# Cube_Mini_8x8x8_LED_Grid_08.net
KiCad netlist of a schematic drawn in EAGLE
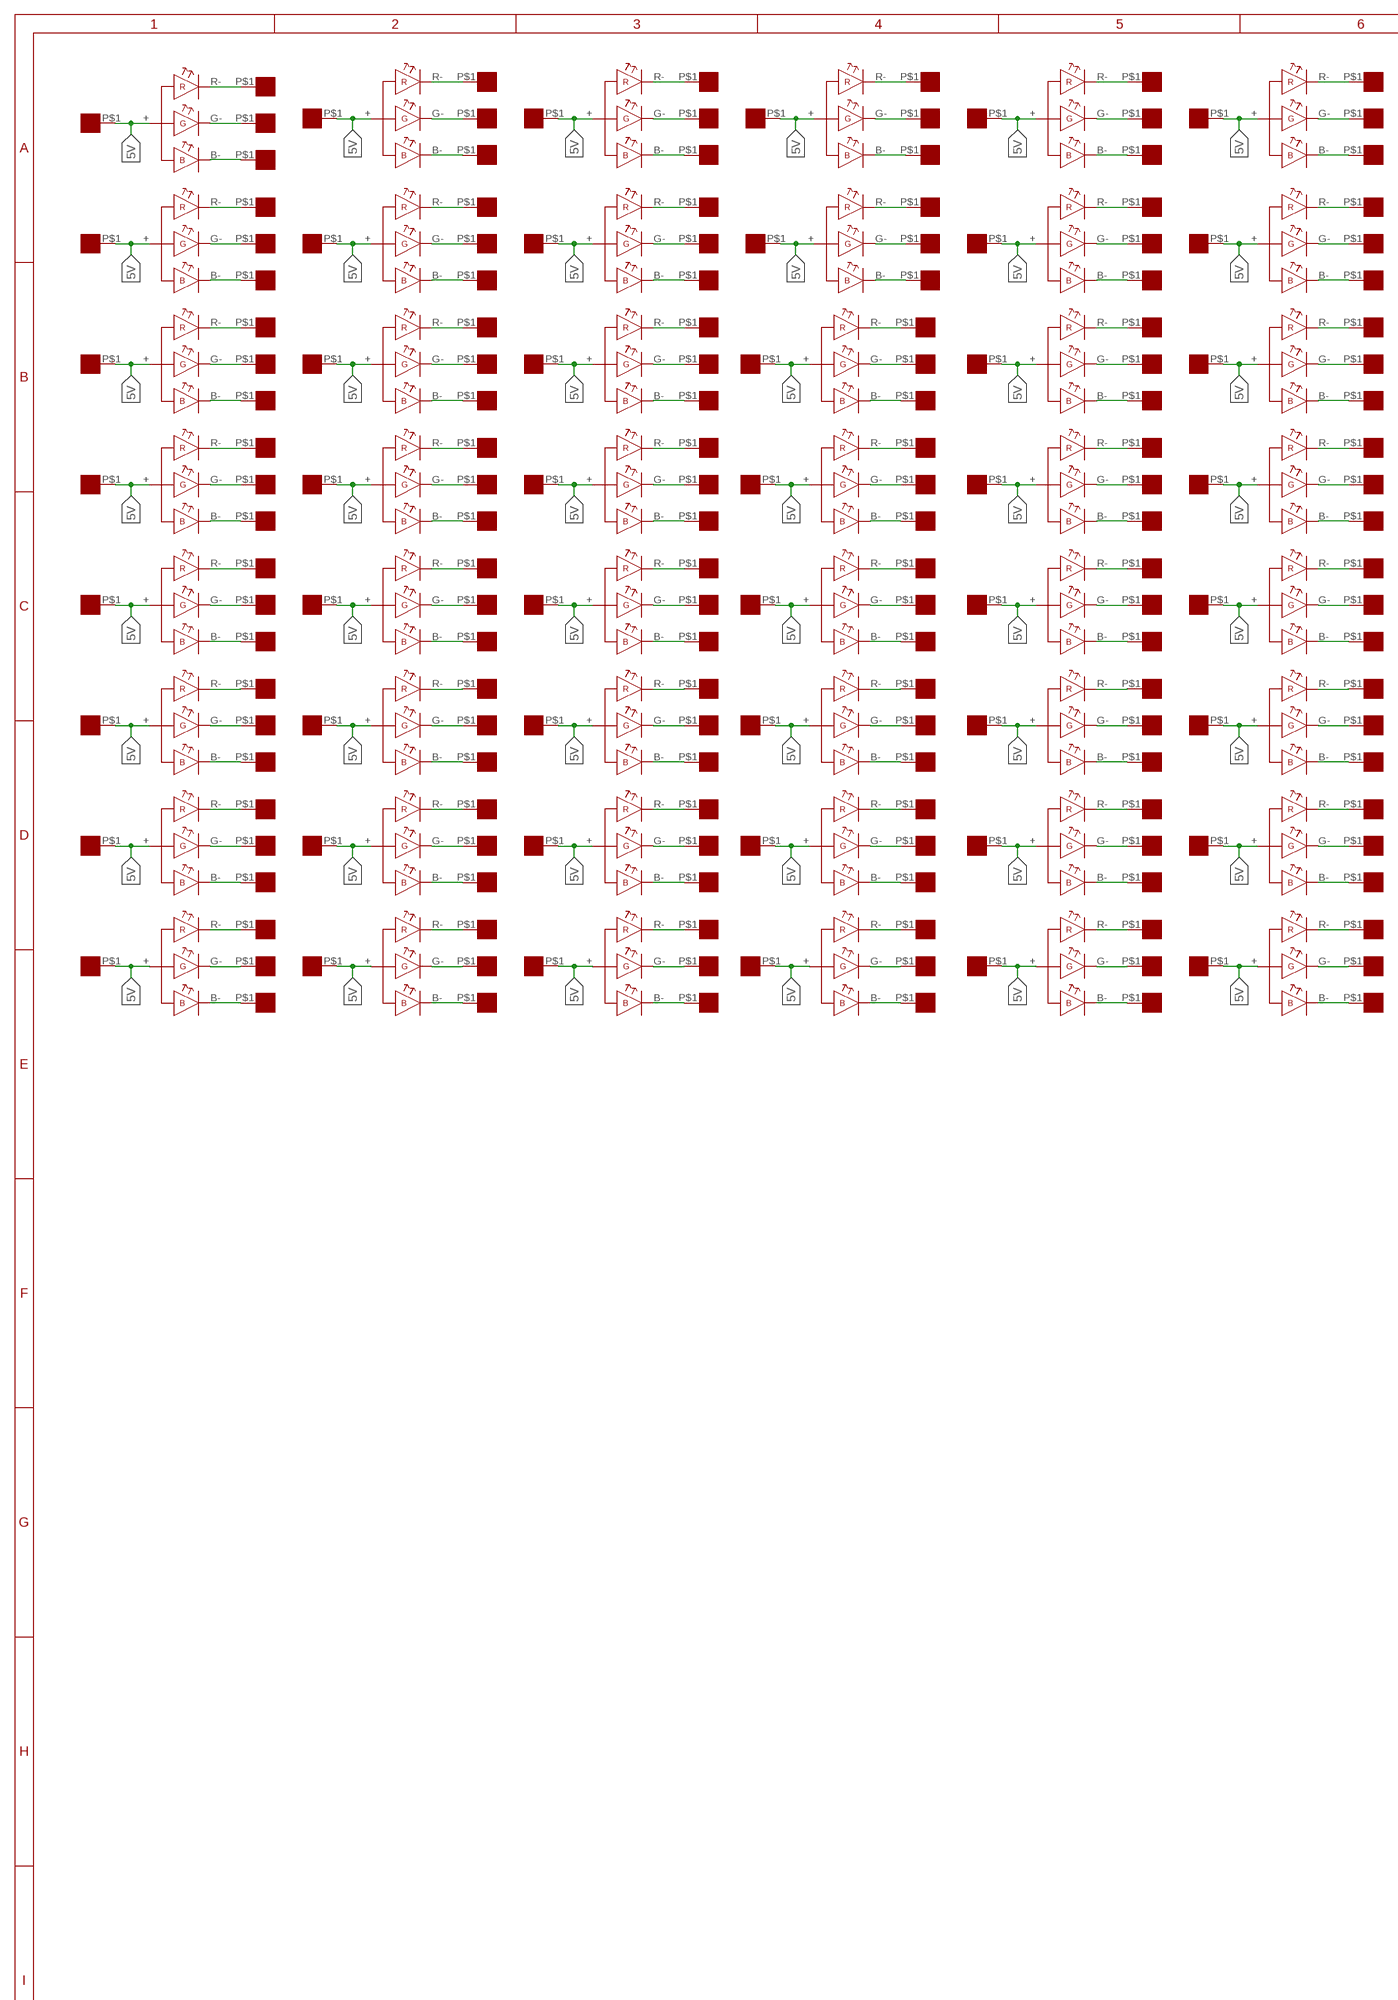
[diagram p0: schematic, sheet 1, part 1 of 2]
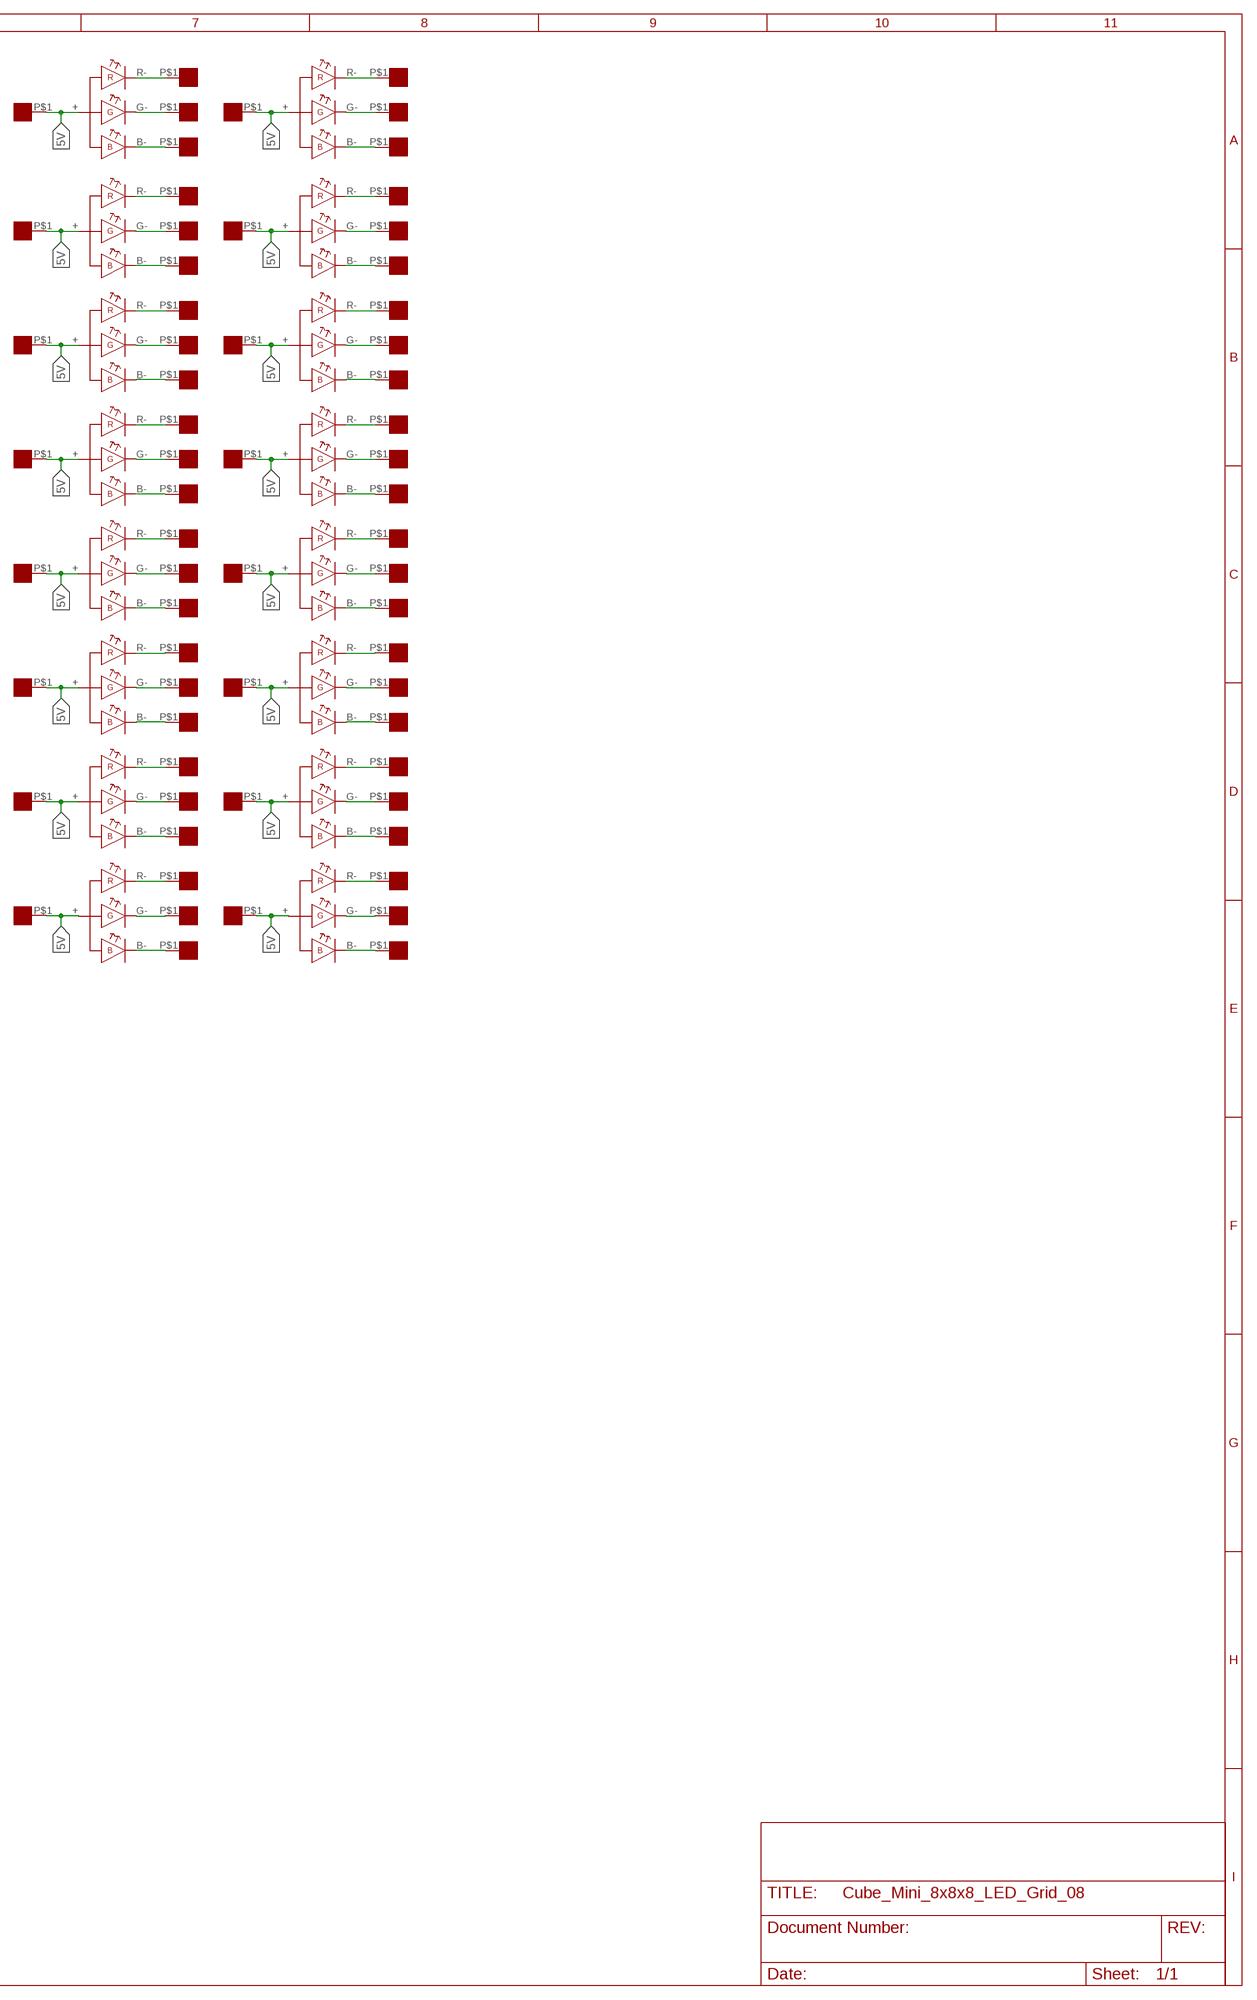
[diagram p1: schematic, sheet 1, part 2 of 2]

(export (version "E")
  (design (tool "Eeschema 10.0.6"))
  (components
    (comp (ref "5V$1")
      (value "05X08PAD")
      (footprint "eagle-import:05X08PAD")
      (libsource (lib "eagle-import") (part "05X08PAD"))
    )
    (comp (ref "5V$2")
      (value "05X08PAD")
      (footprint "eagle-import:05X08PAD")
      (libsource (lib "eagle-import") (part "05X08PAD"))
    )
    (comp (ref "5V$3")
      (value "05X08PAD")
      (footprint "eagle-import:05X08PAD")
      (libsource (lib "eagle-import") (part "05X08PAD"))
    )
    (comp (ref "5V$4")
      (value "05X08PAD")
      (footprint "eagle-import:05X08PAD")
      (libsource (lib "eagle-import") (part "05X08PAD"))
    )
    (comp (ref "5V$5")
      (value "05X08PAD")
      (footprint "eagle-import:05X08PAD")
      (libsource (lib "eagle-import") (part "05X08PAD"))
    )
    (comp (ref "5V$6")
      (value "05X08PAD")
      (footprint "eagle-import:05X08PAD")
      (libsource (lib "eagle-import") (part "05X08PAD"))
    )
    (comp (ref "5V$7")
      (value "05X08PAD")
      (footprint "eagle-import:05X08PAD")
      (libsource (lib "eagle-import") (part "05X08PAD"))
    )
    (comp (ref "5V$8")
      (value "05X08PAD")
      (footprint "eagle-import:05X08PAD")
      (libsource (lib "eagle-import") (part "05X08PAD"))
    )
    (comp (ref "5V$9")
      (value "05X08PAD")
      (footprint "eagle-import:05X08PAD")
      (libsource (lib "eagle-import") (part "05X08PAD"))
    )
    (comp (ref "5V$10")
      (value "05X08PAD")
      (footprint "eagle-import:05X08PAD")
      (libsource (lib "eagle-import") (part "05X08PAD"))
    )
    (comp (ref "5V$11")
      (value "05X08PAD")
      (footprint "eagle-import:05X08PAD")
      (libsource (lib "eagle-import") (part "05X08PAD"))
    )
    (comp (ref "5V$12")
      (value "05X08PAD")
      (footprint "eagle-import:05X08PAD")
      (libsource (lib "eagle-import") (part "05X08PAD"))
    )
    (comp (ref "5V$13")
      (value "05X08PAD")
      (footprint "eagle-import:05X08PAD")
      (libsource (lib "eagle-import") (part "05X08PAD"))
    )
    (comp (ref "5V$14")
      (value "05X08PAD")
      (footprint "eagle-import:05X08PAD")
      (libsource (lib "eagle-import") (part "05X08PAD"))
    )
    (comp (ref "5V$15")
      (value "05X08PAD")
      (footprint "eagle-import:05X08PAD")
      (libsource (lib "eagle-import") (part "05X08PAD"))
    )
    (comp (ref "5V$16")
      (value "05X08PAD")
      (footprint "eagle-import:05X08PAD")
      (libsource (lib "eagle-import") (part "05X08PAD"))
    )
    (comp (ref "5V$17")
      (value "05X08PAD")
      (footprint "eagle-import:05X08PAD")
      (libsource (lib "eagle-import") (part "05X08PAD"))
    )
    (comp (ref "5V$18")
      (value "05X08PAD")
      (footprint "eagle-import:05X08PAD")
      (libsource (lib "eagle-import") (part "05X08PAD"))
    )
    (comp (ref "5V$19")
      (value "05X08PAD")
      (footprint "eagle-import:05X08PAD")
      (libsource (lib "eagle-import") (part "05X08PAD"))
    )
    (comp (ref "5V$20")
      (value "05X08PAD")
      (footprint "eagle-import:05X08PAD")
      (libsource (lib "eagle-import") (part "05X08PAD"))
    )
    (comp (ref "5V$21")
      (value "05X08PAD")
      (footprint "eagle-import:05X08PAD")
      (libsource (lib "eagle-import") (part "05X08PAD"))
    )
    (comp (ref "5V$22")
      (value "05X08PAD")
      (footprint "eagle-import:05X08PAD")
      (libsource (lib "eagle-import") (part "05X08PAD"))
    )
    (comp (ref "5V$23")
      (value "05X08PAD")
      (footprint "eagle-import:05X08PAD")
      (libsource (lib "eagle-import") (part "05X08PAD"))
    )
    (comp (ref "5V$24")
      (value "05X08PAD")
      (footprint "eagle-import:05X08PAD")
      (libsource (lib "eagle-import") (part "05X08PAD"))
    )
    (comp (ref "5V$25")
      (value "05X08PAD")
      (footprint "eagle-import:05X08PAD")
      (libsource (lib "eagle-import") (part "05X08PAD"))
    )
    (comp (ref "5V$26")
      (value "05X08PAD")
      (footprint "eagle-import:05X08PAD")
      (libsource (lib "eagle-import") (part "05X08PAD"))
    )
    (comp (ref "5V$27")
      (value "05X08PAD")
      (footprint "eagle-import:05X08PAD")
      (libsource (lib "eagle-import") (part "05X08PAD"))
    )
    (comp (ref "5V$28")
      (value "05X08PAD")
      (footprint "eagle-import:05X08PAD")
      (libsource (lib "eagle-import") (part "05X08PAD"))
    )
    (comp (ref "5V$29")
      (value "05X08PAD")
      (footprint "eagle-import:05X08PAD")
      (libsource (lib "eagle-import") (part "05X08PAD"))
    )
    (comp (ref "5V$30")
      (value "05X08PAD")
      (footprint "eagle-import:05X08PAD")
      (libsource (lib "eagle-import") (part "05X08PAD"))
    )
    (comp (ref "5V$31")
      (value "05X08PAD")
      (footprint "eagle-import:05X08PAD")
      (libsource (lib "eagle-import") (part "05X08PAD"))
    )
    (comp (ref "5V$32")
      (value "05X08PAD")
      (footprint "eagle-import:05X08PAD")
      (libsource (lib "eagle-import") (part "05X08PAD"))
    )
    (comp (ref "5V$33")
      (value "05X08PAD")
      (footprint "eagle-import:05X08PAD")
      (libsource (lib "eagle-import") (part "05X08PAD"))
    )
    (comp (ref "5V$34")
      (value "05X08PAD")
      (footprint "eagle-import:05X08PAD")
      (libsource (lib "eagle-import") (part "05X08PAD"))
    )
    (comp (ref "5V$35")
      (value "05X08PAD")
      (footprint "eagle-import:05X08PAD")
      (libsource (lib "eagle-import") (part "05X08PAD"))
    )
    (comp (ref "5V$36")
      (value "05X08PAD")
      (footprint "eagle-import:05X08PAD")
      (libsource (lib "eagle-import") (part "05X08PAD"))
    )
    (comp (ref "5V$37")
      (value "05X08PAD")
      (footprint "eagle-import:05X08PAD")
      (libsource (lib "eagle-import") (part "05X08PAD"))
    )
    (comp (ref "5V$38")
      (value "05X08PAD")
      (footprint "eagle-import:05X08PAD")
      (libsource (lib "eagle-import") (part "05X08PAD"))
    )
    (comp (ref "5V$39")
      (value "05X08PAD")
      (footprint "eagle-import:05X08PAD")
      (libsource (lib "eagle-import") (part "05X08PAD"))
    )
    (comp (ref "5V$40")
      (value "05X08PAD")
      (footprint "eagle-import:05X08PAD")
      (libsource (lib "eagle-import") (part "05X08PAD"))
    )
    (comp (ref "5V$41")
      (value "05X08PAD")
      (footprint "eagle-import:05X08PAD")
      (libsource (lib "eagle-import") (part "05X08PAD"))
    )
    (comp (ref "5V$42")
      (value "05X08PAD")
      (footprint "eagle-import:05X08PAD")
      (libsource (lib "eagle-import") (part "05X08PAD"))
    )
    (comp (ref "5V$43")
      (value "05X08PAD")
      (footprint "eagle-import:05X08PAD")
      (libsource (lib "eagle-import") (part "05X08PAD"))
    )
    (comp (ref "5V$44")
      (value "05X08PAD")
      (footprint "eagle-import:05X08PAD")
      (libsource (lib "eagle-import") (part "05X08PAD"))
    )
    (comp (ref "5V$45")
      (value "05X08PAD")
      (footprint "eagle-import:05X08PAD")
      (libsource (lib "eagle-import") (part "05X08PAD"))
    )
    (comp (ref "5V$46")
      (value "05X08PAD")
      (footprint "eagle-import:05X08PAD")
      (libsource (lib "eagle-import") (part "05X08PAD"))
    )
    (comp (ref "5V$47")
      (value "05X08PAD")
      (footprint "eagle-import:05X08PAD")
      (libsource (lib "eagle-import") (part "05X08PAD"))
    )
    (comp (ref "5V$48")
      (value "05X08PAD")
      (footprint "eagle-import:05X08PAD")
      (libsource (lib "eagle-import") (part "05X08PAD"))
    )
    (comp (ref "5V$49")
      (value "05X08PAD")
      (footprint "eagle-import:05X08PAD")
      (libsource (lib "eagle-import") (part "05X08PAD"))
    )
    (comp (ref "5V$50")
      (value "05X08PAD")
      (footprint "eagle-import:05X08PAD")
      (libsource (lib "eagle-import") (part "05X08PAD"))
    )
    (comp (ref "5V$51")
      (value "05X08PAD")
      (footprint "eagle-import:05X08PAD")
      (libsource (lib "eagle-import") (part "05X08PAD"))
    )
    (comp (ref "5V$52")
      (value "05X08PAD")
      (footprint "eagle-import:05X08PAD")
      (libsource (lib "eagle-import") (part "05X08PAD"))
    )
    (comp (ref "5V$53")
      (value "05X08PAD")
      (footprint "eagle-import:05X08PAD")
      (libsource (lib "eagle-import") (part "05X08PAD"))
    )
    (comp (ref "5V$54")
      (value "05X08PAD")
      (footprint "eagle-import:05X08PAD")
      (libsource (lib "eagle-import") (part "05X08PAD"))
    )
    (comp (ref "5V$55")
      (value "05X08PAD")
      (footprint "eagle-import:05X08PAD")
      (libsource (lib "eagle-import") (part "05X08PAD"))
    )
    (comp (ref "5V$56")
      (value "05X08PAD")
      (footprint "eagle-import:05X08PAD")
      (libsource (lib "eagle-import") (part "05X08PAD"))
    )
    (comp (ref "5V$57")
      (value "05X08PAD")
      (footprint "eagle-import:05X08PAD")
      (libsource (lib "eagle-import") (part "05X08PAD"))
    )
    (comp (ref "5V$58")
      (value "05X08PAD")
      (footprint "eagle-import:05X08PAD")
      (libsource (lib "eagle-import") (part "05X08PAD"))
    )
    (comp (ref "5V$59")
      (value "05X08PAD")
      (footprint "eagle-import:05X08PAD")
      (libsource (lib "eagle-import") (part "05X08PAD"))
    )
    (comp (ref "5V$60")
      (value "05X08PAD")
      (footprint "eagle-import:05X08PAD")
      (libsource (lib "eagle-import") (part "05X08PAD"))
    )
    (comp (ref "5V$61")
      (value "05X08PAD")
      (footprint "eagle-import:05X08PAD")
      (libsource (lib "eagle-import") (part "05X08PAD"))
    )
    (comp (ref "5V$62")
      (value "05X08PAD")
      (footprint "eagle-import:05X08PAD")
      (libsource (lib "eagle-import") (part "05X08PAD"))
    )
    (comp (ref "5V$63")
      (value "05X08PAD")
      (footprint "eagle-import:05X08PAD")
      (libsource (lib "eagle-import") (part "05X08PAD"))
    )
    (comp (ref "5V$64")
      (value "05X08PAD")
      (footprint "eagle-import:05X08PAD")
      (libsource (lib "eagle-import") (part "05X08PAD"))
    )
    (comp (ref "B$1")
      (value "05X08PAD")
      (footprint "eagle-import:05X08PAD")
      (libsource (lib "eagle-import") (part "05X08PAD"))
    )
    (comp (ref "B$2")
      (value "05X08PAD")
      (footprint "eagle-import:05X08PAD")
      (libsource (lib "eagle-import") (part "05X08PAD"))
    )
    (comp (ref "B$3")
      (value "05X08PAD")
      (footprint "eagle-import:05X08PAD")
      (libsource (lib "eagle-import") (part "05X08PAD"))
    )
    (comp (ref "B$4")
      (value "05X08PAD")
      (footprint "eagle-import:05X08PAD")
      (libsource (lib "eagle-import") (part "05X08PAD"))
    )
    (comp (ref "B$5")
      (value "05X08PAD")
      (footprint "eagle-import:05X08PAD")
      (libsource (lib "eagle-import") (part "05X08PAD"))
    )
    (comp (ref "B$6")
      (value "05X08PAD")
      (footprint "eagle-import:05X08PAD")
      (libsource (lib "eagle-import") (part "05X08PAD"))
    )
    (comp (ref "B$7")
      (value "05X08PAD")
      (footprint "eagle-import:05X08PAD")
      (libsource (lib "eagle-import") (part "05X08PAD"))
    )
    (comp (ref "B$8")
      (value "05X08PAD")
      (footprint "eagle-import:05X08PAD")
      (libsource (lib "eagle-import") (part "05X08PAD"))
    )
    (comp (ref "B$9")
      (value "05X08PAD")
      (footprint "eagle-import:05X08PAD")
      (libsource (lib "eagle-import") (part "05X08PAD"))
    )
    (comp (ref "B$10")
      (value "05X08PAD")
      (footprint "eagle-import:05X08PAD")
      (libsource (lib "eagle-import") (part "05X08PAD"))
    )
    (comp (ref "B$11")
      (value "05X08PAD")
      (footprint "eagle-import:05X08PAD")
      (libsource (lib "eagle-import") (part "05X08PAD"))
    )
    (comp (ref "B$12")
      (value "05X08PAD")
      (footprint "eagle-import:05X08PAD")
      (libsource (lib "eagle-import") (part "05X08PAD"))
    )
    (comp (ref "B$13")
      (value "05X08PAD")
      (footprint "eagle-import:05X08PAD")
      (libsource (lib "eagle-import") (part "05X08PAD"))
    )
    (comp (ref "B$14")
      (value "05X08PAD")
      (footprint "eagle-import:05X08PAD")
      (libsource (lib "eagle-import") (part "05X08PAD"))
    )
    (comp (ref "B$15")
      (value "05X08PAD")
      (footprint "eagle-import:05X08PAD")
      (libsource (lib "eagle-import") (part "05X08PAD"))
    )
    (comp (ref "B$16")
      (value "05X08PAD")
      (footprint "eagle-import:05X08PAD")
      (libsource (lib "eagle-import") (part "05X08PAD"))
    )
    (comp (ref "B$17")
      (value "05X08PAD")
      (footprint "eagle-import:05X08PAD")
      (libsource (lib "eagle-import") (part "05X08PAD"))
    )
    (comp (ref "B$18")
      (value "05X08PAD")
      (footprint "eagle-import:05X08PAD")
      (libsource (lib "eagle-import") (part "05X08PAD"))
    )
    (comp (ref "B$19")
      (value "05X08PAD")
      (footprint "eagle-import:05X08PAD")
      (libsource (lib "eagle-import") (part "05X08PAD"))
    )
    (comp (ref "B$20")
      (value "05X08PAD")
      (footprint "eagle-import:05X08PAD")
      (libsource (lib "eagle-import") (part "05X08PAD"))
    )
    (comp (ref "B$21")
      (value "05X08PAD")
      (footprint "eagle-import:05X08PAD")
      (libsource (lib "eagle-import") (part "05X08PAD"))
    )
    (comp (ref "B$22")
      (value "05X08PAD")
      (footprint "eagle-import:05X08PAD")
      (libsource (lib "eagle-import") (part "05X08PAD"))
    )
    (comp (ref "B$23")
      (value "05X08PAD")
      (footprint "eagle-import:05X08PAD")
      (libsource (lib "eagle-import") (part "05X08PAD"))
    )
    (comp (ref "B$24")
      (value "05X08PAD")
      (footprint "eagle-import:05X08PAD")
      (libsource (lib "eagle-import") (part "05X08PAD"))
    )
    (comp (ref "B$25")
      (value "05X08PAD")
      (footprint "eagle-import:05X08PAD")
      (libsource (lib "eagle-import") (part "05X08PAD"))
    )
    (comp (ref "B$26")
      (value "05X08PAD")
      (footprint "eagle-import:05X08PAD")
      (libsource (lib "eagle-import") (part "05X08PAD"))
    )
    (comp (ref "B$27")
      (value "05X08PAD")
      (footprint "eagle-import:05X08PAD")
      (libsource (lib "eagle-import") (part "05X08PAD"))
    )
    (comp (ref "B$28")
      (value "05X08PAD")
      (footprint "eagle-import:05X08PAD")
      (libsource (lib "eagle-import") (part "05X08PAD"))
    )
    (comp (ref "B$29")
      (value "05X08PAD")
      (footprint "eagle-import:05X08PAD")
      (libsource (lib "eagle-import") (part "05X08PAD"))
    )
    (comp (ref "B$30")
      (value "05X08PAD")
      (footprint "eagle-import:05X08PAD")
      (libsource (lib "eagle-import") (part "05X08PAD"))
    )
    (comp (ref "B$31")
      (value "05X08PAD")
      (footprint "eagle-import:05X08PAD")
      (libsource (lib "eagle-import") (part "05X08PAD"))
    )
    (comp (ref "B$32")
      (value "05X08PAD")
      (footprint "eagle-import:05X08PAD")
      (libsource (lib "eagle-import") (part "05X08PAD"))
    )
    (comp (ref "B$33")
      (value "05X08PAD")
      (footprint "eagle-import:05X08PAD")
      (libsource (lib "eagle-import") (part "05X08PAD"))
    )
    (comp (ref "B$34")
      (value "05X08PAD")
      (footprint "eagle-import:05X08PAD")
      (libsource (lib "eagle-import") (part "05X08PAD"))
    )
    (comp (ref "B$35")
      (value "05X08PAD")
      (footprint "eagle-import:05X08PAD")
      (libsource (lib "eagle-import") (part "05X08PAD"))
    )
    (comp (ref "B$36")
      (value "05X08PAD")
      (footprint "eagle-import:05X08PAD")
      (libsource (lib "eagle-import") (part "05X08PAD"))
    )
    (comp (ref "B$37")
      (value "05X08PAD")
      (footprint "eagle-import:05X08PAD")
      (libsource (lib "eagle-import") (part "05X08PAD"))
    )
    (comp (ref "B$38")
      (value "05X08PAD")
      (footprint "eagle-import:05X08PAD")
      (libsource (lib "eagle-import") (part "05X08PAD"))
    )
    (comp (ref "B$39")
      (value "05X08PAD")
      (footprint "eagle-import:05X08PAD")
      (libsource (lib "eagle-import") (part "05X08PAD"))
    )
    (comp (ref "B$40")
      (value "05X08PAD")
      (footprint "eagle-import:05X08PAD")
      (libsource (lib "eagle-import") (part "05X08PAD"))
    )
    (comp (ref "B$41")
      (value "05X08PAD")
      (footprint "eagle-import:05X08PAD")
      (libsource (lib "eagle-import") (part "05X08PAD"))
    )
    (comp (ref "B$42")
      (value "05X08PAD")
      (footprint "eagle-import:05X08PAD")
      (libsource (lib "eagle-import") (part "05X08PAD"))
    )
    (comp (ref "B$43")
      (value "05X08PAD")
      (footprint "eagle-import:05X08PAD")
      (libsource (lib "eagle-import") (part "05X08PAD"))
    )
    (comp (ref "B$44")
      (value "05X08PAD")
      (footprint "eagle-import:05X08PAD")
      (libsource (lib "eagle-import") (part "05X08PAD"))
    )
    (comp (ref "B$45")
      (value "05X08PAD")
      (footprint "eagle-import:05X08PAD")
      (libsource (lib "eagle-import") (part "05X08PAD"))
    )
    (comp (ref "B$46")
      (value "05X08PAD")
      (footprint "eagle-import:05X08PAD")
      (libsource (lib "eagle-import") (part "05X08PAD"))
    )
    (comp (ref "B$47")
      (value "05X08PAD")
      (footprint "eagle-import:05X08PAD")
      (libsource (lib "eagle-import") (part "05X08PAD"))
    )
    (comp (ref "B$48")
      (value "05X08PAD")
      (footprint "eagle-import:05X08PAD")
      (libsource (lib "eagle-import") (part "05X08PAD"))
    )
    (comp (ref "B$49")
      (value "05X08PAD")
      (footprint "eagle-import:05X08PAD")
      (libsource (lib "eagle-import") (part "05X08PAD"))
    )
    (comp (ref "B$50")
      (value "05X08PAD")
      (footprint "eagle-import:05X08PAD")
      (libsource (lib "eagle-import") (part "05X08PAD"))
    )
    (comp (ref "B$51")
      (value "05X08PAD")
      (footprint "eagle-import:05X08PAD")
      (libsource (lib "eagle-import") (part "05X08PAD"))
    )
    (comp (ref "B$52")
      (value "05X08PAD")
      (footprint "eagle-import:05X08PAD")
      (libsource (lib "eagle-import") (part "05X08PAD"))
    )
    (comp (ref "B$53")
      (value "05X08PAD")
      (footprint "eagle-import:05X08PAD")
      (libsource (lib "eagle-import") (part "05X08PAD"))
    )
    (comp (ref "B$54")
      (value "05X08PAD")
      (footprint "eagle-import:05X08PAD")
      (libsource (lib "eagle-import") (part "05X08PAD"))
    )
    (comp (ref "B$55")
      (value "05X08PAD")
      (footprint "eagle-import:05X08PAD")
      (libsource (lib "eagle-import") (part "05X08PAD"))
    )
    (comp (ref "B$56")
      (value "05X08PAD")
      (footprint "eagle-import:05X08PAD")
      (libsource (lib "eagle-import") (part "05X08PAD"))
    )
    (comp (ref "B$57")
      (value "05X08PAD")
      (footprint "eagle-import:05X08PAD")
      (libsource (lib "eagle-import") (part "05X08PAD"))
    )
    (comp (ref "B$58")
      (value "05X08PAD")
      (footprint "eagle-import:05X08PAD")
      (libsource (lib "eagle-import") (part "05X08PAD"))
    )
    (comp (ref "B$59")
      (value "05X08PAD")
      (footprint "eagle-import:05X08PAD")
      (libsource (lib "eagle-import") (part "05X08PAD"))
    )
    (comp (ref "B$60")
      (value "05X08PAD")
      (footprint "eagle-import:05X08PAD")
      (libsource (lib "eagle-import") (part "05X08PAD"))
    )
    (comp (ref "B$61")
      (value "05X08PAD")
      (footprint "eagle-import:05X08PAD")
      (libsource (lib "eagle-import") (part "05X08PAD"))
    )
    (comp (ref "B$62")
      (value "05X08PAD")
      (footprint "eagle-import:05X08PAD")
      (libsource (lib "eagle-import") (part "05X08PAD"))
    )
    (comp (ref "B$63")
      (value "05X08PAD")
      (footprint "eagle-import:05X08PAD")
      (libsource (lib "eagle-import") (part "05X08PAD"))
    )
    (comp (ref "B$64")
      (value "05X08PAD")
      (footprint "eagle-import:05X08PAD")
      (libsource (lib "eagle-import") (part "05X08PAD"))
    )
    (comp (ref "G$1")
      (value "05X08PAD")
      (footprint "eagle-import:05X08PAD")
      (libsource (lib "eagle-import") (part "05X08PAD"))
    )
    (comp (ref "G$2")
      (value "05X08PAD")
      (footprint "eagle-import:05X08PAD")
      (libsource (lib "eagle-import") (part "05X08PAD"))
    )
    (comp (ref "G$3")
      (value "05X08PAD")
      (footprint "eagle-import:05X08PAD")
      (libsource (lib "eagle-import") (part "05X08PAD"))
    )
    (comp (ref "G$4")
      (value "05X08PAD")
      (footprint "eagle-import:05X08PAD")
      (libsource (lib "eagle-import") (part "05X08PAD"))
    )
    (comp (ref "G$5")
      (value "05X08PAD")
      (footprint "eagle-import:05X08PAD")
      (libsource (lib "eagle-import") (part "05X08PAD"))
    )
    (comp (ref "G$6")
      (value "05X08PAD")
      (footprint "eagle-import:05X08PAD")
      (libsource (lib "eagle-import") (part "05X08PAD"))
    )
    (comp (ref "G$7")
      (value "05X08PAD")
      (footprint "eagle-import:05X08PAD")
      (libsource (lib "eagle-import") (part "05X08PAD"))
    )
    (comp (ref "G$8")
      (value "05X08PAD")
      (footprint "eagle-import:05X08PAD")
      (libsource (lib "eagle-import") (part "05X08PAD"))
    )
    (comp (ref "G$9")
      (value "05X08PAD")
      (footprint "eagle-import:05X08PAD")
      (libsource (lib "eagle-import") (part "05X08PAD"))
    )
    (comp (ref "G$10")
      (value "05X08PAD")
      (footprint "eagle-import:05X08PAD")
      (libsource (lib "eagle-import") (part "05X08PAD"))
    )
    (comp (ref "G$11")
      (value "05X08PAD")
      (footprint "eagle-import:05X08PAD")
      (libsource (lib "eagle-import") (part "05X08PAD"))
    )
    (comp (ref "G$12")
      (value "05X08PAD")
      (footprint "eagle-import:05X08PAD")
      (libsource (lib "eagle-import") (part "05X08PAD"))
    )
    (comp (ref "G$13")
      (value "05X08PAD")
      (footprint "eagle-import:05X08PAD")
      (libsource (lib "eagle-import") (part "05X08PAD"))
    )
    (comp (ref "G$14")
      (value "05X08PAD")
      (footprint "eagle-import:05X08PAD")
      (libsource (lib "eagle-import") (part "05X08PAD"))
    )
    (comp (ref "G$15")
      (value "05X08PAD")
      (footprint "eagle-import:05X08PAD")
      (libsource (lib "eagle-import") (part "05X08PAD"))
    )
    (comp (ref "G$16")
      (value "05X08PAD")
      (footprint "eagle-import:05X08PAD")
      (libsource (lib "eagle-import") (part "05X08PAD"))
    )
    (comp (ref "G$17")
      (value "05X08PAD")
      (footprint "eagle-import:05X08PAD")
      (libsource (lib "eagle-import") (part "05X08PAD"))
    )
    (comp (ref "G$18")
      (value "05X08PAD")
      (footprint "eagle-import:05X08PAD")
      (libsource (lib "eagle-import") (part "05X08PAD"))
    )
    (comp (ref "G$19")
      (value "05X08PAD")
      (footprint "eagle-import:05X08PAD")
      (libsource (lib "eagle-import") (part "05X08PAD"))
    )
    (comp (ref "G$20")
      (value "05X08PAD")
      (footprint "eagle-import:05X08PAD")
      (libsource (lib "eagle-import") (part "05X08PAD"))
    )
    (comp (ref "G$21")
      (value "05X08PAD")
      (footprint "eagle-import:05X08PAD")
      (libsource (lib "eagle-import") (part "05X08PAD"))
    )
    (comp (ref "G$22")
      (value "05X08PAD")
      (footprint "eagle-import:05X08PAD")
      (libsource (lib "eagle-import") (part "05X08PAD"))
    )
    (comp (ref "G$23")
      (value "05X08PAD")
      (footprint "eagle-import:05X08PAD")
      (libsource (lib "eagle-import") (part "05X08PAD"))
    )
    (comp (ref "G$24")
      (value "05X08PAD")
      (footprint "eagle-import:05X08PAD")
      (libsource (lib "eagle-import") (part "05X08PAD"))
    )
    (comp (ref "G$25")
      (value "05X08PAD")
      (footprint "eagle-import:05X08PAD")
      (libsource (lib "eagle-import") (part "05X08PAD"))
    )
    (comp (ref "G$26")
      (value "05X08PAD")
      (footprint "eagle-import:05X08PAD")
      (libsource (lib "eagle-import") (part "05X08PAD"))
    )
    (comp (ref "G$27")
      (value "05X08PAD")
      (footprint "eagle-import:05X08PAD")
      (libsource (lib "eagle-import") (part "05X08PAD"))
    )
    (comp (ref "G$28")
      (value "05X08PAD")
      (footprint "eagle-import:05X08PAD")
      (libsource (lib "eagle-import") (part "05X08PAD"))
    )
    (comp (ref "G$29")
      (value "05X08PAD")
      (footprint "eagle-import:05X08PAD")
      (libsource (lib "eagle-import") (part "05X08PAD"))
    )
    (comp (ref "G$30")
      (value "05X08PAD")
      (footprint "eagle-import:05X08PAD")
      (libsource (lib "eagle-import") (part "05X08PAD"))
    )
    (comp (ref "G$31")
      (value "05X08PAD")
      (footprint "eagle-import:05X08PAD")
      (libsource (lib "eagle-import") (part "05X08PAD"))
    )
    (comp (ref "G$32")
      (value "05X08PAD")
      (footprint "eagle-import:05X08PAD")
      (libsource (lib "eagle-import") (part "05X08PAD"))
    )
    (comp (ref "G$33")
      (value "05X08PAD")
      (footprint "eagle-import:05X08PAD")
      (libsource (lib "eagle-import") (part "05X08PAD"))
    )
    (comp (ref "G$34")
      (value "05X08PAD")
      (footprint "eagle-import:05X08PAD")
      (libsource (lib "eagle-import") (part "05X08PAD"))
    )
    (comp (ref "G$35")
      (value "05X08PAD")
      (footprint "eagle-import:05X08PAD")
      (libsource (lib "eagle-import") (part "05X08PAD"))
    )
    (comp (ref "G$36")
      (value "05X08PAD")
      (footprint "eagle-import:05X08PAD")
      (libsource (lib "eagle-import") (part "05X08PAD"))
    )
    (comp (ref "G$37")
      (value "05X08PAD")
      (footprint "eagle-import:05X08PAD")
      (libsource (lib "eagle-import") (part "05X08PAD"))
    )
    (comp (ref "G$38")
      (value "05X08PAD")
      (footprint "eagle-import:05X08PAD")
      (libsource (lib "eagle-import") (part "05X08PAD"))
    )
    (comp (ref "G$39")
      (value "05X08PAD")
      (footprint "eagle-import:05X08PAD")
      (libsource (lib "eagle-import") (part "05X08PAD"))
    )
    (comp (ref "G$40")
      (value "05X08PAD")
      (footprint "eagle-import:05X08PAD")
      (libsource (lib "eagle-import") (part "05X08PAD"))
    )
    (comp (ref "G$41")
      (value "05X08PAD")
      (footprint "eagle-import:05X08PAD")
      (libsource (lib "eagle-import") (part "05X08PAD"))
    )
    (comp (ref "G$42")
      (value "05X08PAD")
      (footprint "eagle-import:05X08PAD")
      (libsource (lib "eagle-import") (part "05X08PAD"))
    )
    (comp (ref "G$43")
      (value "05X08PAD")
      (footprint "eagle-import:05X08PAD")
      (libsource (lib "eagle-import") (part "05X08PAD"))
    )
    (comp (ref "G$44")
      (value "05X08PAD")
      (footprint "eagle-import:05X08PAD")
      (libsource (lib "eagle-import") (part "05X08PAD"))
    )
    (comp (ref "G$45")
      (value "05X08PAD")
      (footprint "eagle-import:05X08PAD")
      (libsource (lib "eagle-import") (part "05X08PAD"))
    )
    (comp (ref "G$46")
      (value "05X08PAD")
      (footprint "eagle-import:05X08PAD")
      (libsource (lib "eagle-import") (part "05X08PAD"))
    )
    (comp (ref "G$47")
      (value "05X08PAD")
      (footprint "eagle-import:05X08PAD")
      (libsource (lib "eagle-import") (part "05X08PAD"))
    )
    (comp (ref "G$48")
      (value "05X08PAD")
      (footprint "eagle-import:05X08PAD")
      (libsource (lib "eagle-import") (part "05X08PAD"))
    )
    (comp (ref "G$49")
      (value "05X08PAD")
      (footprint "eagle-import:05X08PAD")
      (libsource (lib "eagle-import") (part "05X08PAD"))
    )
    (comp (ref "G$50")
      (value "05X08PAD")
      (footprint "eagle-import:05X08PAD")
      (libsource (lib "eagle-import") (part "05X08PAD"))
    )
    (comp (ref "G$51")
      (value "05X08PAD")
      (footprint "eagle-import:05X08PAD")
      (libsource (lib "eagle-import") (part "05X08PAD"))
    )
    (comp (ref "G$52")
      (value "05X08PAD")
      (footprint "eagle-import:05X08PAD")
      (libsource (lib "eagle-import") (part "05X08PAD"))
    )
    (comp (ref "G$53")
      (value "05X08PAD")
      (footprint "eagle-import:05X08PAD")
      (libsource (lib "eagle-import") (part "05X08PAD"))
    )
    (comp (ref "G$54")
      (value "05X08PAD")
      (footprint "eagle-import:05X08PAD")
      (libsource (lib "eagle-import") (part "05X08PAD"))
    )
    (comp (ref "G$55")
      (value "05X08PAD")
      (footprint "eagle-import:05X08PAD")
      (libsource (lib "eagle-import") (part "05X08PAD"))
    )
    (comp (ref "G$56")
      (value "05X08PAD")
      (footprint "eagle-import:05X08PAD")
      (libsource (lib "eagle-import") (part "05X08PAD"))
    )
    (comp (ref "G$57")
      (value "05X08PAD")
      (footprint "eagle-import:05X08PAD")
      (libsource (lib "eagle-import") (part "05X08PAD"))
    )
    (comp (ref "G$58")
      (value "05X08PAD")
      (footprint "eagle-import:05X08PAD")
      (libsource (lib "eagle-import") (part "05X08PAD"))
    )
    (comp (ref "G$59")
      (value "05X08PAD")
      (footprint "eagle-import:05X08PAD")
      (libsource (lib "eagle-import") (part "05X08PAD"))
    )
    (comp (ref "G$60")
      (value "05X08PAD")
      (footprint "eagle-import:05X08PAD")
      (libsource (lib "eagle-import") (part "05X08PAD"))
    )
    (comp (ref "G$61")
      (value "05X08PAD")
      (footprint "eagle-import:05X08PAD")
      (libsource (lib "eagle-import") (part "05X08PAD"))
    )
    (comp (ref "G$62")
      (value "05X08PAD")
      (footprint "eagle-import:05X08PAD")
      (libsource (lib "eagle-import") (part "05X08PAD"))
    )
    (comp (ref "G$63")
      (value "05X08PAD")
      (footprint "eagle-import:05X08PAD")
      (libsource (lib "eagle-import") (part "05X08PAD"))
    )
    (comp (ref "G$64")
      (value "05X08PAD")
      (footprint "eagle-import:05X08PAD")
      (libsource (lib "eagle-import") (part "05X08PAD"))
    )
    (comp (ref "R$1")
      (value "05X08PAD")
      (footprint "eagle-import:05X08PAD")
      (libsource (lib "eagle-import") (part "05X08PAD"))
    )
    (comp (ref "R$2")
      (value "05X08PAD")
      (footprint "eagle-import:05X08PAD")
      (libsource (lib "eagle-import") (part "05X08PAD"))
    )
    (comp (ref "R$3")
      (value "05X08PAD")
      (footprint "eagle-import:05X08PAD")
      (libsource (lib "eagle-import") (part "05X08PAD"))
    )
    (comp (ref "R$4")
      (value "05X08PAD")
      (footprint "eagle-import:05X08PAD")
      (libsource (lib "eagle-import") (part "05X08PAD"))
    )
    (comp (ref "R$5")
      (value "05X08PAD")
      (footprint "eagle-import:05X08PAD")
      (libsource (lib "eagle-import") (part "05X08PAD"))
    )
    (comp (ref "R$6")
      (value "05X08PAD")
      (footprint "eagle-import:05X08PAD")
      (libsource (lib "eagle-import") (part "05X08PAD"))
    )
    (comp (ref "R$7")
      (value "05X08PAD")
      (footprint "eagle-import:05X08PAD")
      (libsource (lib "eagle-import") (part "05X08PAD"))
    )
    (comp (ref "R$8")
      (value "05X08PAD")
      (footprint "eagle-import:05X08PAD")
      (libsource (lib "eagle-import") (part "05X08PAD"))
    )
    (comp (ref "R$9")
      (value "05X08PAD")
      (footprint "eagle-import:05X08PAD")
      (libsource (lib "eagle-import") (part "05X08PAD"))
    )
    (comp (ref "R$10")
      (value "05X08PAD")
      (footprint "eagle-import:05X08PAD")
      (libsource (lib "eagle-import") (part "05X08PAD"))
    )
    (comp (ref "R$11")
      (value "05X08PAD")
      (footprint "eagle-import:05X08PAD")
      (libsource (lib "eagle-import") (part "05X08PAD"))
    )
    (comp (ref "R$12")
      (value "05X08PAD")
      (footprint "eagle-import:05X08PAD")
      (libsource (lib "eagle-import") (part "05X08PAD"))
    )
    (comp (ref "R$13")
      (value "05X08PAD")
      (footprint "eagle-import:05X08PAD")
      (libsource (lib "eagle-import") (part "05X08PAD"))
    )
    (comp (ref "R$14")
      (value "05X08PAD")
      (footprint "eagle-import:05X08PAD")
      (libsource (lib "eagle-import") (part "05X08PAD"))
    )
    (comp (ref "R$15")
      (value "05X08PAD")
      (footprint "eagle-import:05X08PAD")
      (libsource (lib "eagle-import") (part "05X08PAD"))
    )
    (comp (ref "R$16")
      (value "05X08PAD")
      (footprint "eagle-import:05X08PAD")
      (libsource (lib "eagle-import") (part "05X08PAD"))
    )
    (comp (ref "R$17")
      (value "05X08PAD")
      (footprint "eagle-import:05X08PAD")
      (libsource (lib "eagle-import") (part "05X08PAD"))
    )
    (comp (ref "R$18")
      (value "05X08PAD")
      (footprint "eagle-import:05X08PAD")
      (libsource (lib "eagle-import") (part "05X08PAD"))
    )
    (comp (ref "R$19")
      (value "05X08PAD")
      (footprint "eagle-import:05X08PAD")
      (libsource (lib "eagle-import") (part "05X08PAD"))
    )
    (comp (ref "R$20")
      (value "05X08PAD")
      (footprint "eagle-import:05X08PAD")
      (libsource (lib "eagle-import") (part "05X08PAD"))
    )
    (comp (ref "R$21")
      (value "05X08PAD")
      (footprint "eagle-import:05X08PAD")
      (libsource (lib "eagle-import") (part "05X08PAD"))
    )
    (comp (ref "R$22")
      (value "05X08PAD")
      (footprint "eagle-import:05X08PAD")
      (libsource (lib "eagle-import") (part "05X08PAD"))
    )
    (comp (ref "R$23")
      (value "05X08PAD")
      (footprint "eagle-import:05X08PAD")
      (libsource (lib "eagle-import") (part "05X08PAD"))
    )
    (comp (ref "R$24")
      (value "05X08PAD")
      (footprint "eagle-import:05X08PAD")
      (libsource (lib "eagle-import") (part "05X08PAD"))
    )
    (comp (ref "R$25")
      (value "05X08PAD")
      (footprint "eagle-import:05X08PAD")
      (libsource (lib "eagle-import") (part "05X08PAD"))
    )
    (comp (ref "R$26")
      (value "05X08PAD")
      (footprint "eagle-import:05X08PAD")
      (libsource (lib "eagle-import") (part "05X08PAD"))
    )
    (comp (ref "R$27")
      (value "05X08PAD")
      (footprint "eagle-import:05X08PAD")
      (libsource (lib "eagle-import") (part "05X08PAD"))
    )
    (comp (ref "R$28")
      (value "05X08PAD")
      (footprint "eagle-import:05X08PAD")
      (libsource (lib "eagle-import") (part "05X08PAD"))
    )
    (comp (ref "R$29")
      (value "05X08PAD")
      (footprint "eagle-import:05X08PAD")
      (libsource (lib "eagle-import") (part "05X08PAD"))
    )
    (comp (ref "R$30")
      (value "05X08PAD")
      (footprint "eagle-import:05X08PAD")
      (libsource (lib "eagle-import") (part "05X08PAD"))
    )
    (comp (ref "R$31")
      (value "05X08PAD")
      (footprint "eagle-import:05X08PAD")
      (libsource (lib "eagle-import") (part "05X08PAD"))
    )
    (comp (ref "R$32")
      (value "05X08PAD")
      (footprint "eagle-import:05X08PAD")
      (libsource (lib "eagle-import") (part "05X08PAD"))
    )
    (comp (ref "R$33")
      (value "05X08PAD")
      (footprint "eagle-import:05X08PAD")
      (libsource (lib "eagle-import") (part "05X08PAD"))
    )
    (comp (ref "R$34")
      (value "05X08PAD")
      (footprint "eagle-import:05X08PAD")
      (libsource (lib "eagle-import") (part "05X08PAD"))
    )
    (comp (ref "R$35")
      (value "05X08PAD")
      (footprint "eagle-import:05X08PAD")
      (libsource (lib "eagle-import") (part "05X08PAD"))
    )
    (comp (ref "R$36")
      (value "05X08PAD")
      (footprint "eagle-import:05X08PAD")
      (libsource (lib "eagle-import") (part "05X08PAD"))
    )
    (comp (ref "R$37")
      (value "05X08PAD")
      (footprint "eagle-import:05X08PAD")
      (libsource (lib "eagle-import") (part "05X08PAD"))
    )
    (comp (ref "R$38")
      (value "05X08PAD")
      (footprint "eagle-import:05X08PAD")
      (libsource (lib "eagle-import") (part "05X08PAD"))
    )
    (comp (ref "R$39")
      (value "05X08PAD")
      (footprint "eagle-import:05X08PAD")
      (libsource (lib "eagle-import") (part "05X08PAD"))
    )
    (comp (ref "R$40")
      (value "05X08PAD")
      (footprint "eagle-import:05X08PAD")
      (libsource (lib "eagle-import") (part "05X08PAD"))
    )
    (comp (ref "R$41")
      (value "05X08PAD")
      (footprint "eagle-import:05X08PAD")
      (libsource (lib "eagle-import") (part "05X08PAD"))
    )
    (comp (ref "R$42")
      (value "05X08PAD")
      (footprint "eagle-import:05X08PAD")
      (libsource (lib "eagle-import") (part "05X08PAD"))
    )
    (comp (ref "R$43")
      (value "05X08PAD")
      (footprint "eagle-import:05X08PAD")
      (libsource (lib "eagle-import") (part "05X08PAD"))
    )
    (comp (ref "R$44")
      (value "05X08PAD")
      (footprint "eagle-import:05X08PAD")
      (libsource (lib "eagle-import") (part "05X08PAD"))
    )
    (comp (ref "R$45")
      (value "05X08PAD")
      (footprint "eagle-import:05X08PAD")
      (libsource (lib "eagle-import") (part "05X08PAD"))
    )
    (comp (ref "R$46")
      (value "05X08PAD")
      (footprint "eagle-import:05X08PAD")
      (libsource (lib "eagle-import") (part "05X08PAD"))
    )
    (comp (ref "R$47")
      (value "05X08PAD")
      (footprint "eagle-import:05X08PAD")
      (libsource (lib "eagle-import") (part "05X08PAD"))
    )
    (comp (ref "R$48")
      (value "05X08PAD")
      (footprint "eagle-import:05X08PAD")
      (libsource (lib "eagle-import") (part "05X08PAD"))
    )
    (comp (ref "R$49")
      (value "05X08PAD")
      (footprint "eagle-import:05X08PAD")
      (libsource (lib "eagle-import") (part "05X08PAD"))
    )
    (comp (ref "R$50")
      (value "05X08PAD")
      (footprint "eagle-import:05X08PAD")
      (libsource (lib "eagle-import") (part "05X08PAD"))
    )
    (comp (ref "R$51")
      (value "05X08PAD")
      (footprint "eagle-import:05X08PAD")
      (libsource (lib "eagle-import") (part "05X08PAD"))
    )
    (comp (ref "R$52")
      (value "05X08PAD")
      (footprint "eagle-import:05X08PAD")
      (libsource (lib "eagle-import") (part "05X08PAD"))
    )
    (comp (ref "R$53")
      (value "05X08PAD")
      (footprint "eagle-import:05X08PAD")
      (libsource (lib "eagle-import") (part "05X08PAD"))
    )
    (comp (ref "R$54")
      (value "05X08PAD")
      (footprint "eagle-import:05X08PAD")
      (libsource (lib "eagle-import") (part "05X08PAD"))
    )
    (comp (ref "R$55")
      (value "05X08PAD")
      (footprint "eagle-import:05X08PAD")
      (libsource (lib "eagle-import") (part "05X08PAD"))
    )
    (comp (ref "R$56")
      (value "05X08PAD")
      (footprint "eagle-import:05X08PAD")
      (libsource (lib "eagle-import") (part "05X08PAD"))
    )
    (comp (ref "R$57")
      (value "05X08PAD")
      (footprint "eagle-import:05X08PAD")
      (libsource (lib "eagle-import") (part "05X08PAD"))
    )
    (comp (ref "R$58")
      (value "05X08PAD")
      (footprint "eagle-import:05X08PAD")
      (libsource (lib "eagle-import") (part "05X08PAD"))
    )
    (comp (ref "R$59")
      (value "05X08PAD")
      (footprint "eagle-import:05X08PAD")
      (libsource (lib "eagle-import") (part "05X08PAD"))
    )
    (comp (ref "R$60")
      (value "05X08PAD")
      (footprint "eagle-import:05X08PAD")
      (libsource (lib "eagle-import") (part "05X08PAD"))
    )
    (comp (ref "R$61")
      (value "05X08PAD")
      (footprint "eagle-import:05X08PAD")
      (libsource (lib "eagle-import") (part "05X08PAD"))
    )
    (comp (ref "R$62")
      (value "05X08PAD")
      (footprint "eagle-import:05X08PAD")
      (libsource (lib "eagle-import") (part "05X08PAD"))
    )
    (comp (ref "R$63")
      (value "05X08PAD")
      (footprint "eagle-import:05X08PAD")
      (libsource (lib "eagle-import") (part "05X08PAD"))
    )
    (comp (ref "R$64")
      (value "05X08PAD")
      (footprint "eagle-import:05X08PAD")
      (libsource (lib "eagle-import") (part "05X08PAD"))
    )
    (comp (ref "U$1")
      (value "B1010RGBT")
      (footprint "eagle-import:B1010RGBT")
      (libsource (lib "eagle-import") (part "B1010RGBT"))
    )
    (comp (ref "U$2")
      (value "B1010RGBT")
      (footprint "eagle-import:B1010RGBT")
      (libsource (lib "eagle-import") (part "B1010RGBT"))
    )
    (comp (ref "U$3")
      (value "B1010RGBT")
      (footprint "eagle-import:B1010RGBT")
      (libsource (lib "eagle-import") (part "B1010RGBT"))
    )
    (comp (ref "U$4")
      (value "B1010RGBT")
      (footprint "eagle-import:B1010RGBT")
      (libsource (lib "eagle-import") (part "B1010RGBT"))
    )
    (comp (ref "U$5")
      (value "B1010RGBT")
      (footprint "eagle-import:B1010RGBT")
      (libsource (lib "eagle-import") (part "B1010RGBT"))
    )
    (comp (ref "U$6")
      (value "B1010RGBT")
      (footprint "eagle-import:B1010RGBT")
      (libsource (lib "eagle-import") (part "B1010RGBT"))
    )
    (comp (ref "U$7")
      (value "B1010RGBT")
      (footprint "eagle-import:B1010RGBT")
      (libsource (lib "eagle-import") (part "B1010RGBT"))
    )
    (comp (ref "U$8")
      (value "B1010RGBT")
      (footprint "eagle-import:B1010RGBT")
      (libsource (lib "eagle-import") (part "B1010RGBT"))
    )
    (comp (ref "U$9")
      (value "B1010RGBT")
      (footprint "eagle-import:B1010RGBT")
      (libsource (lib "eagle-import") (part "B1010RGBT"))
    )
    (comp (ref "U$10")
      (value "B1010RGBT")
      (footprint "eagle-import:B1010RGBT")
      (libsource (lib "eagle-import") (part "B1010RGBT"))
    )
    (comp (ref "U$11")
      (value "B1010RGBT")
      (footprint "eagle-import:B1010RGBT")
      (libsource (lib "eagle-import") (part "B1010RGBT"))
    )
    (comp (ref "U$12")
      (value "B1010RGBT")
      (footprint "eagle-import:B1010RGBT")
      (libsource (lib "eagle-import") (part "B1010RGBT"))
    )
    (comp (ref "U$13")
      (value "B1010RGBT")
      (footprint "eagle-import:B1010RGBT")
      (libsource (lib "eagle-import") (part "B1010RGBT"))
    )
    (comp (ref "U$14")
      (value "B1010RGBT")
      (footprint "eagle-import:B1010RGBT")
      (libsource (lib "eagle-import") (part "B1010RGBT"))
    )
    (comp (ref "U$15")
      (value "B1010RGBT")
      (footprint "eagle-import:B1010RGBT")
      (libsource (lib "eagle-import") (part "B1010RGBT"))
    )
    (comp (ref "U$16")
      (value "B1010RGBT")
      (footprint "eagle-import:B1010RGBT")
      (libsource (lib "eagle-import") (part "B1010RGBT"))
    )
    (comp (ref "U$17")
      (value "B1010RGBT")
      (footprint "eagle-import:B1010RGBT")
      (libsource (lib "eagle-import") (part "B1010RGBT"))
    )
    (comp (ref "U$18")
      (value "B1010RGBT")
      (footprint "eagle-import:B1010RGBT")
      (libsource (lib "eagle-import") (part "B1010RGBT"))
    )
    (comp (ref "U$19")
      (value "B1010RGBT")
      (footprint "eagle-import:B1010RGBT")
      (libsource (lib "eagle-import") (part "B1010RGBT"))
    )
    (comp (ref "U$20")
      (value "B1010RGBT")
      (footprint "eagle-import:B1010RGBT")
      (libsource (lib "eagle-import") (part "B1010RGBT"))
    )
    (comp (ref "U$21")
      (value "B1010RGBT")
      (footprint "eagle-import:B1010RGBT")
      (libsource (lib "eagle-import") (part "B1010RGBT"))
    )
    (comp (ref "U$22")
      (value "B1010RGBT")
      (footprint "eagle-import:B1010RGBT")
      (libsource (lib "eagle-import") (part "B1010RGBT"))
    )
    (comp (ref "U$23")
      (value "B1010RGBT")
      (footprint "eagle-import:B1010RGBT")
      (libsource (lib "eagle-import") (part "B1010RGBT"))
    )
    (comp (ref "U$24")
      (value "B1010RGBT")
      (footprint "eagle-import:B1010RGBT")
      (libsource (lib "eagle-import") (part "B1010RGBT"))
    )
    (comp (ref "U$25")
      (value "B1010RGBT")
      (footprint "eagle-import:B1010RGBT")
      (libsource (lib "eagle-import") (part "B1010RGBT"))
    )
    (comp (ref "U$26")
      (value "B1010RGBT")
      (footprint "eagle-import:B1010RGBT")
      (libsource (lib "eagle-import") (part "B1010RGBT"))
    )
    (comp (ref "U$27")
      (value "B1010RGBT")
      (footprint "eagle-import:B1010RGBT")
      (libsource (lib "eagle-import") (part "B1010RGBT"))
    )
    (comp (ref "U$28")
      (value "B1010RGBT")
      (footprint "eagle-import:B1010RGBT")
      (libsource (lib "eagle-import") (part "B1010RGBT"))
    )
    (comp (ref "U$29")
      (value "B1010RGBT")
      (footprint "eagle-import:B1010RGBT")
      (libsource (lib "eagle-import") (part "B1010RGBT"))
    )
    (comp (ref "U$30")
      (value "B1010RGBT")
      (footprint "eagle-import:B1010RGBT")
      (libsource (lib "eagle-import") (part "B1010RGBT"))
    )
    (comp (ref "U$31")
      (value "B1010RGBT")
      (footprint "eagle-import:B1010RGBT")
      (libsource (lib "eagle-import") (part "B1010RGBT"))
    )
    (comp (ref "U$32")
      (value "B1010RGBT")
      (footprint "eagle-import:B1010RGBT")
      (libsource (lib "eagle-import") (part "B1010RGBT"))
    )
    (comp (ref "U$33")
      (value "B1010RGBT")
      (footprint "eagle-import:B1010RGBT")
      (libsource (lib "eagle-import") (part "B1010RGBT"))
    )
    (comp (ref "U$34")
      (value "B1010RGBT")
      (footprint "eagle-import:B1010RGBT")
      (libsource (lib "eagle-import") (part "B1010RGBT"))
    )
    (comp (ref "U$35")
      (value "B1010RGBT")
      (footprint "eagle-import:B1010RGBT")
      (libsource (lib "eagle-import") (part "B1010RGBT"))
    )
    (comp (ref "U$36")
      (value "B1010RGBT")
      (footprint "eagle-import:B1010RGBT")
      (libsource (lib "eagle-import") (part "B1010RGBT"))
    )
    (comp (ref "U$37")
      (value "B1010RGBT")
      (footprint "eagle-import:B1010RGBT")
      (libsource (lib "eagle-import") (part "B1010RGBT"))
    )
    (comp (ref "U$38")
      (value "B1010RGBT")
      (footprint "eagle-import:B1010RGBT")
      (libsource (lib "eagle-import") (part "B1010RGBT"))
    )
    (comp (ref "U$39")
      (value "B1010RGBT")
      (footprint "eagle-import:B1010RGBT")
      (libsource (lib "eagle-import") (part "B1010RGBT"))
    )
    (comp (ref "U$40")
      (value "B1010RGBT")
      (footprint "eagle-import:B1010RGBT")
      (libsource (lib "eagle-import") (part "B1010RGBT"))
    )
    (comp (ref "U$41")
      (value "B1010RGBT")
      (footprint "eagle-import:B1010RGBT")
      (libsource (lib "eagle-import") (part "B1010RGBT"))
    )
    (comp (ref "U$42")
      (value "B1010RGBT")
      (footprint "eagle-import:B1010RGBT")
      (libsource (lib "eagle-import") (part "B1010RGBT"))
    )
    (comp (ref "U$43")
      (value "B1010RGBT")
      (footprint "eagle-import:B1010RGBT")
      (libsource (lib "eagle-import") (part "B1010RGBT"))
    )
    (comp (ref "U$44")
      (value "B1010RGBT")
      (footprint "eagle-import:B1010RGBT")
      (libsource (lib "eagle-import") (part "B1010RGBT"))
    )
    (comp (ref "U$45")
      (value "B1010RGBT")
      (footprint "eagle-import:B1010RGBT")
      (libsource (lib "eagle-import") (part "B1010RGBT"))
    )
    (comp (ref "U$46")
      (value "B1010RGBT")
      (footprint "eagle-import:B1010RGBT")
      (libsource (lib "eagle-import") (part "B1010RGBT"))
    )
    (comp (ref "U$47")
      (value "B1010RGBT")
      (footprint "eagle-import:B1010RGBT")
      (libsource (lib "eagle-import") (part "B1010RGBT"))
    )
    (comp (ref "U$48")
      (value "B1010RGBT")
      (footprint "eagle-import:B1010RGBT")
      (libsource (lib "eagle-import") (part "B1010RGBT"))
    )
    (comp (ref "U$49")
      (value "B1010RGBT")
      (footprint "eagle-import:B1010RGBT")
      (libsource (lib "eagle-import") (part "B1010RGBT"))
    )
    (comp (ref "U$50")
      (value "B1010RGBT")
      (footprint "eagle-import:B1010RGBT")
      (libsource (lib "eagle-import") (part "B1010RGBT"))
    )
    (comp (ref "U$51")
      (value "B1010RGBT")
      (footprint "eagle-import:B1010RGBT")
      (libsource (lib "eagle-import") (part "B1010RGBT"))
    )
    (comp (ref "U$52")
      (value "B1010RGBT")
      (footprint "eagle-import:B1010RGBT")
      (libsource (lib "eagle-import") (part "B1010RGBT"))
    )
    (comp (ref "U$53")
      (value "B1010RGBT")
      (footprint "eagle-import:B1010RGBT")
      (libsource (lib "eagle-import") (part "B1010RGBT"))
    )
    (comp (ref "U$54")
      (value "B1010RGBT")
      (footprint "eagle-import:B1010RGBT")
      (libsource (lib "eagle-import") (part "B1010RGBT"))
    )
    (comp (ref "U$55")
      (value "B1010RGBT")
      (footprint "eagle-import:B1010RGBT")
      (libsource (lib "eagle-import") (part "B1010RGBT"))
    )
    (comp (ref "U$56")
      (value "B1010RGBT")
      (footprint "eagle-import:B1010RGBT")
      (libsource (lib "eagle-import") (part "B1010RGBT"))
    )
    (comp (ref "U$57")
      (value "B1010RGBT")
      (footprint "eagle-import:B1010RGBT")
      (libsource (lib "eagle-import") (part "B1010RGBT"))
    )
    (comp (ref "U$58")
      (value "B1010RGBT")
      (footprint "eagle-import:B1010RGBT")
      (libsource (lib "eagle-import") (part "B1010RGBT"))
    )
    (comp (ref "U$59")
      (value "B1010RGBT")
      (footprint "eagle-import:B1010RGBT")
      (libsource (lib "eagle-import") (part "B1010RGBT"))
    )
    (comp (ref "U$60")
      (value "B1010RGBT")
      (footprint "eagle-import:B1010RGBT")
      (libsource (lib "eagle-import") (part "B1010RGBT"))
    )
    (comp (ref "U$61")
      (value "B1010RGBT")
      (footprint "eagle-import:B1010RGBT")
      (libsource (lib "eagle-import") (part "B1010RGBT"))
    )
    (comp (ref "U$62")
      (value "B1010RGBT")
      (footprint "eagle-import:B1010RGBT")
      (libsource (lib "eagle-import") (part "B1010RGBT"))
    )
    (comp (ref "U$63")
      (value "B1010RGBT")
      (footprint "eagle-import:B1010RGBT")
      (libsource (lib "eagle-import") (part "B1010RGBT"))
    )
    (comp (ref "U$64")
      (value "B1010RGBT")
      (footprint "eagle-import:B1010RGBT")
      (libsource (lib "eagle-import") (part "B1010RGBT"))
    )
  )
  (nets
    (net (code "1") (name "5V") (class "Default")
      (node (ref "5V$1") (pin "P$1") (pinfunction "P$1_P$1") (pintype "bidirectional"))
      (node (ref "5V$10") (pin "P$1") (pinfunction "P$1_P$1") (pintype "bidirectional"))
      (node (ref "5V$11") (pin "P$1") (pinfunction "P$1_P$1") (pintype "bidirectional"))
      (node (ref "5V$12") (pin "P$1") (pinfunction "P$1_P$1") (pintype "bidirectional"))
      (node (ref "5V$13") (pin "P$1") (pinfunction "P$1_P$1") (pintype "bidirectional"))
      (node (ref "5V$14") (pin "P$1") (pinfunction "P$1_P$1") (pintype "bidirectional"))
      (node (ref "5V$15") (pin "P$1") (pinfunction "P$1_P$1") (pintype "bidirectional"))
      (node (ref "5V$16") (pin "P$1") (pinfunction "P$1_P$1") (pintype "bidirectional"))
      (node (ref "5V$17") (pin "P$1") (pinfunction "P$1_P$1") (pintype "bidirectional"))
      (node (ref "5V$18") (pin "P$1") (pinfunction "P$1_P$1") (pintype "bidirectional"))
      (node (ref "5V$19") (pin "P$1") (pinfunction "P$1_P$1") (pintype "bidirectional"))
      (node (ref "5V$2") (pin "P$1") (pinfunction "P$1_P$1") (pintype "bidirectional"))
      (node (ref "5V$20") (pin "P$1") (pinfunction "P$1_P$1") (pintype "bidirectional"))
      (node (ref "5V$21") (pin "P$1") (pinfunction "P$1_P$1") (pintype "bidirectional"))
      (node (ref "5V$22") (pin "P$1") (pinfunction "P$1_P$1") (pintype "bidirectional"))
      (node (ref "5V$23") (pin "P$1") (pinfunction "P$1_P$1") (pintype "bidirectional"))
      (node (ref "5V$24") (pin "P$1") (pinfunction "P$1_P$1") (pintype "bidirectional"))
      (node (ref "5V$25") (pin "P$1") (pinfunction "P$1_P$1") (pintype "bidirectional"))
      (node (ref "5V$26") (pin "P$1") (pinfunction "P$1_P$1") (pintype "bidirectional"))
      (node (ref "5V$27") (pin "P$1") (pinfunction "P$1_P$1") (pintype "bidirectional"))
      (node (ref "5V$28") (pin "P$1") (pinfunction "P$1_P$1") (pintype "bidirectional"))
      (node (ref "5V$29") (pin "P$1") (pinfunction "P$1_P$1") (pintype "bidirectional"))
      (node (ref "5V$3") (pin "P$1") (pinfunction "P$1_P$1") (pintype "bidirectional"))
      (node (ref "5V$30") (pin "P$1") (pinfunction "P$1_P$1") (pintype "bidirectional"))
      (node (ref "5V$31") (pin "P$1") (pinfunction "P$1_P$1") (pintype "bidirectional"))
      (node (ref "5V$32") (pin "P$1") (pinfunction "P$1_P$1") (pintype "bidirectional"))
      (node (ref "5V$33") (pin "P$1") (pinfunction "P$1_P$1") (pintype "bidirectional"))
      (node (ref "5V$34") (pin "P$1") (pinfunction "P$1_P$1") (pintype "bidirectional"))
      (node (ref "5V$35") (pin "P$1") (pinfunction "P$1_P$1") (pintype "bidirectional"))
      (node (ref "5V$36") (pin "P$1") (pinfunction "P$1_P$1") (pintype "bidirectional"))
      (node (ref "5V$37") (pin "P$1") (pinfunction "P$1_P$1") (pintype "bidirectional"))
      (node (ref "5V$38") (pin "P$1") (pinfunction "P$1_P$1") (pintype "bidirectional"))
      (node (ref "5V$39") (pin "P$1") (pinfunction "P$1_P$1") (pintype "bidirectional"))
      (node (ref "5V$4") (pin "P$1") (pinfunction "P$1_P$1") (pintype "bidirectional"))
      (node (ref "5V$40") (pin "P$1") (pinfunction "P$1_P$1") (pintype "bidirectional"))
      (node (ref "5V$41") (pin "P$1") (pinfunction "P$1_P$1") (pintype "bidirectional"))
      (node (ref "5V$42") (pin "P$1") (pinfunction "P$1_P$1") (pintype "bidirectional"))
      (node (ref "5V$43") (pin "P$1") (pinfunction "P$1_P$1") (pintype "bidirectional"))
      (node (ref "5V$44") (pin "P$1") (pinfunction "P$1_P$1") (pintype "bidirectional"))
      (node (ref "5V$45") (pin "P$1") (pinfunction "P$1_P$1") (pintype "bidirectional"))
      (node (ref "5V$46") (pin "P$1") (pinfunction "P$1_P$1") (pintype "bidirectional"))
      (node (ref "5V$47") (pin "P$1") (pinfunction "P$1_P$1") (pintype "bidirectional"))
      (node (ref "5V$48") (pin "P$1") (pinfunction "P$1_P$1") (pintype "bidirectional"))
      (node (ref "5V$49") (pin "P$1") (pinfunction "P$1_P$1") (pintype "bidirectional"))
      (node (ref "5V$5") (pin "P$1") (pinfunction "P$1_P$1") (pintype "bidirectional"))
      (node (ref "5V$50") (pin "P$1") (pinfunction "P$1_P$1") (pintype "bidirectional"))
      (node (ref "5V$51") (pin "P$1") (pinfunction "P$1_P$1") (pintype "bidirectional"))
      (node (ref "5V$52") (pin "P$1") (pinfunction "P$1_P$1") (pintype "bidirectional"))
      (node (ref "5V$53") (pin "P$1") (pinfunction "P$1_P$1") (pintype "bidirectional"))
      (node (ref "5V$54") (pin "P$1") (pinfunction "P$1_P$1") (pintype "bidirectional"))
      (node (ref "5V$55") (pin "P$1") (pinfunction "P$1_P$1") (pintype "bidirectional"))
      (node (ref "5V$56") (pin "P$1") (pinfunction "P$1_P$1") (pintype "bidirectional"))
      (node (ref "5V$57") (pin "P$1") (pinfunction "P$1_P$1") (pintype "bidirectional"))
      (node (ref "5V$58") (pin "P$1") (pinfunction "P$1_P$1") (pintype "bidirectional"))
      (node (ref "5V$59") (pin "P$1") (pinfunction "P$1_P$1") (pintype "bidirectional"))
      (node (ref "5V$6") (pin "P$1") (pinfunction "P$1_P$1") (pintype "bidirectional"))
      (node (ref "5V$60") (pin "P$1") (pinfunction "P$1_P$1") (pintype "bidirectional"))
      (node (ref "5V$61") (pin "P$1") (pinfunction "P$1_P$1") (pintype "bidirectional"))
      (node (ref "5V$62") (pin "P$1") (pinfunction "P$1_P$1") (pintype "bidirectional"))
      (node (ref "5V$63") (pin "P$1") (pinfunction "P$1_P$1") (pintype "bidirectional"))
      (node (ref "5V$64") (pin "P$1") (pinfunction "P$1_P$1") (pintype "bidirectional"))
      (node (ref "5V$7") (pin "P$1") (pinfunction "P$1_P$1") (pintype "bidirectional"))
      (node (ref "5V$8") (pin "P$1") (pinfunction "P$1_P$1") (pintype "bidirectional"))
      (node (ref "5V$9") (pin "P$1") (pinfunction "P$1_P$1") (pintype "bidirectional"))
      (node (ref "U$1") (pin "+") (pinfunction "+_+") (pintype "bidirectional"))
      (node (ref "U$10") (pin "+") (pinfunction "+_+") (pintype "bidirectional"))
      (node (ref "U$11") (pin "+") (pinfunction "+_+") (pintype "bidirectional"))
      (node (ref "U$12") (pin "+") (pinfunction "+_+") (pintype "bidirectional"))
      (node (ref "U$13") (pin "+") (pinfunction "+_+") (pintype "bidirectional"))
      (node (ref "U$14") (pin "+") (pinfunction "+_+") (pintype "bidirectional"))
      (node (ref "U$15") (pin "+") (pinfunction "+_+") (pintype "bidirectional"))
      (node (ref "U$16") (pin "+") (pinfunction "+_+") (pintype "bidirectional"))
      (node (ref "U$17") (pin "+") (pinfunction "+_+") (pintype "bidirectional"))
      (node (ref "U$18") (pin "+") (pinfunction "+_+") (pintype "bidirectional"))
      (node (ref "U$19") (pin "+") (pinfunction "+_+") (pintype "bidirectional"))
      (node (ref "U$2") (pin "+") (pinfunction "+_+") (pintype "bidirectional"))
      (node (ref "U$20") (pin "+") (pinfunction "+_+") (pintype "bidirectional"))
      (node (ref "U$21") (pin "+") (pinfunction "+_+") (pintype "bidirectional"))
      (node (ref "U$22") (pin "+") (pinfunction "+_+") (pintype "bidirectional"))
      (node (ref "U$23") (pin "+") (pinfunction "+_+") (pintype "bidirectional"))
      (node (ref "U$24") (pin "+") (pinfunction "+_+") (pintype "bidirectional"))
      (node (ref "U$25") (pin "+") (pinfunction "+_+") (pintype "bidirectional"))
      (node (ref "U$26") (pin "+") (pinfunction "+_+") (pintype "bidirectional"))
      (node (ref "U$27") (pin "+") (pinfunction "+_+") (pintype "bidirectional"))
      (node (ref "U$28") (pin "+") (pinfunction "+_+") (pintype "bidirectional"))
      (node (ref "U$29") (pin "+") (pinfunction "+_+") (pintype "bidirectional"))
      (node (ref "U$3") (pin "+") (pinfunction "+_+") (pintype "bidirectional"))
      (node (ref "U$30") (pin "+") (pinfunction "+_+") (pintype "bidirectional"))
      (node (ref "U$31") (pin "+") (pinfunction "+_+") (pintype "bidirectional"))
      (node (ref "U$32") (pin "+") (pinfunction "+_+") (pintype "bidirectional"))
      (node (ref "U$33") (pin "+") (pinfunction "+_+") (pintype "bidirectional"))
      (node (ref "U$34") (pin "+") (pinfunction "+_+") (pintype "bidirectional"))
      (node (ref "U$35") (pin "+") (pinfunction "+_+") (pintype "bidirectional"))
      (node (ref "U$36") (pin "+") (pinfunction "+_+") (pintype "bidirectional"))
      (node (ref "U$37") (pin "+") (pinfunction "+_+") (pintype "bidirectional"))
      (node (ref "U$38") (pin "+") (pinfunction "+_+") (pintype "bidirectional"))
      (node (ref "U$39") (pin "+") (pinfunction "+_+") (pintype "bidirectional"))
      (node (ref "U$4") (pin "+") (pinfunction "+_+") (pintype "bidirectional"))
      (node (ref "U$40") (pin "+") (pinfunction "+_+") (pintype "bidirectional"))
      (node (ref "U$41") (pin "+") (pinfunction "+_+") (pintype "bidirectional"))
      (node (ref "U$42") (pin "+") (pinfunction "+_+") (pintype "bidirectional"))
      (node (ref "U$43") (pin "+") (pinfunction "+_+") (pintype "bidirectional"))
      (node (ref "U$44") (pin "+") (pinfunction "+_+") (pintype "bidirectional"))
      (node (ref "U$45") (pin "+") (pinfunction "+_+") (pintype "bidirectional"))
      (node (ref "U$46") (pin "+") (pinfunction "+_+") (pintype "bidirectional"))
      (node (ref "U$47") (pin "+") (pinfunction "+_+") (pintype "bidirectional"))
      (node (ref "U$48") (pin "+") (pinfunction "+_+") (pintype "bidirectional"))
      (node (ref "U$49") (pin "+") (pinfunction "+_+") (pintype "bidirectional"))
      (node (ref "U$5") (pin "+") (pinfunction "+_+") (pintype "bidirectional"))
      (node (ref "U$50") (pin "+") (pinfunction "+_+") (pintype "bidirectional"))
      (node (ref "U$51") (pin "+") (pinfunction "+_+") (pintype "bidirectional"))
      (node (ref "U$52") (pin "+") (pinfunction "+_+") (pintype "bidirectional"))
      (node (ref "U$53") (pin "+") (pinfunction "+_+") (pintype "bidirectional"))
      (node (ref "U$54") (pin "+") (pinfunction "+_+") (pintype "bidirectional"))
      (node (ref "U$55") (pin "+") (pinfunction "+_+") (pintype "bidirectional"))
      (node (ref "U$56") (pin "+") (pinfunction "+_+") (pintype "bidirectional"))
      (node (ref "U$57") (pin "+") (pinfunction "+_+") (pintype "bidirectional"))
      (node (ref "U$58") (pin "+") (pinfunction "+_+") (pintype "bidirectional"))
      (node (ref "U$59") (pin "+") (pinfunction "+_+") (pintype "bidirectional"))
      (node (ref "U$6") (pin "+") (pinfunction "+_+") (pintype "bidirectional"))
      (node (ref "U$60") (pin "+") (pinfunction "+_+") (pintype "bidirectional"))
      (node (ref "U$61") (pin "+") (pinfunction "+_+") (pintype "bidirectional"))
      (node (ref "U$62") (pin "+") (pinfunction "+_+") (pintype "bidirectional"))
      (node (ref "U$63") (pin "+") (pinfunction "+_+") (pintype "bidirectional"))
      (node (ref "U$64") (pin "+") (pinfunction "+_+") (pintype "bidirectional"))
      (node (ref "U$7") (pin "+") (pinfunction "+_+") (pintype "bidirectional"))
      (node (ref "U$8") (pin "+") (pinfunction "+_+") (pintype "bidirectional"))
      (node (ref "U$9") (pin "+") (pinfunction "+_+") (pintype "bidirectional"))
    )
    (net (code "2") (name "Net-(B$1-PadP$1)") (class "Default")
      (node (ref "B$1") (pin "P$1") (pinfunction "P$1_P$1") (pintype "bidirectional"))
      (node (ref "U$1") (pin "B-") (pinfunction "B-_B-") (pintype "bidirectional"))
    )
    (net (code "3") (name "Net-(B$2-PadP$1)") (class "Default")
      (node (ref "B$2") (pin "P$1") (pinfunction "P$1_P$1") (pintype "bidirectional"))
      (node (ref "U$2") (pin "B-") (pinfunction "B-_B-") (pintype "bidirectional"))
    )
    (net (code "4") (name "Net-(B$3-PadP$1)") (class "Default")
      (node (ref "B$3") (pin "P$1") (pinfunction "P$1_P$1") (pintype "bidirectional"))
      (node (ref "U$3") (pin "B-") (pinfunction "B-_B-") (pintype "bidirectional"))
    )
    (net (code "5") (name "Net-(B$4-PadP$1)") (class "Default")
      (node (ref "B$4") (pin "P$1") (pinfunction "P$1_P$1") (pintype "bidirectional"))
      (node (ref "U$4") (pin "B-") (pinfunction "B-_B-") (pintype "bidirectional"))
    )
    (net (code "6") (name "Net-(B$5-PadP$1)") (class "Default")
      (node (ref "B$5") (pin "P$1") (pinfunction "P$1_P$1") (pintype "bidirectional"))
      (node (ref "U$5") (pin "B-") (pinfunction "B-_B-") (pintype "bidirectional"))
    )
    (net (code "7") (name "Net-(B$6-PadP$1)") (class "Default")
      (node (ref "B$6") (pin "P$1") (pinfunction "P$1_P$1") (pintype "bidirectional"))
      (node (ref "U$6") (pin "B-") (pinfunction "B-_B-") (pintype "bidirectional"))
    )
    (net (code "8") (name "Net-(B$7-PadP$1)") (class "Default")
      (node (ref "B$7") (pin "P$1") (pinfunction "P$1_P$1") (pintype "bidirectional"))
      (node (ref "U$7") (pin "B-") (pinfunction "B-_B-") (pintype "bidirectional"))
    )
    (net (code "9") (name "Net-(B$8-PadP$1)") (class "Default")
      (node (ref "B$8") (pin "P$1") (pinfunction "P$1_P$1") (pintype "bidirectional"))
      (node (ref "U$8") (pin "B-") (pinfunction "B-_B-") (pintype "bidirectional"))
    )
    (net (code "10") (name "Net-(B$9-PadP$1)") (class "Default")
      (node (ref "B$9") (pin "P$1") (pinfunction "P$1_P$1") (pintype "bidirectional"))
      (node (ref "U$9") (pin "B-") (pinfunction "B-_B-") (pintype "bidirectional"))
    )
    (net (code "11") (name "Net-(B$10-PadP$1)") (class "Default")
      (node (ref "B$10") (pin "P$1") (pinfunction "P$1_P$1") (pintype "bidirectional"))
      (node (ref "U$10") (pin "B-") (pinfunction "B-_B-") (pintype "bidirectional"))
    )
    (net (code "12") (name "Net-(B$11-PadP$1)") (class "Default")
      (node (ref "B$11") (pin "P$1") (pinfunction "P$1_P$1") (pintype "bidirectional"))
      (node (ref "U$11") (pin "B-") (pinfunction "B-_B-") (pintype "bidirectional"))
    )
    (net (code "13") (name "Net-(B$12-PadP$1)") (class "Default")
      (node (ref "B$12") (pin "P$1") (pinfunction "P$1_P$1") (pintype "bidirectional"))
      (node (ref "U$12") (pin "B-") (pinfunction "B-_B-") (pintype "bidirectional"))
    )
    (net (code "14") (name "Net-(B$13-PadP$1)") (class "Default")
      (node (ref "B$13") (pin "P$1") (pinfunction "P$1_P$1") (pintype "bidirectional"))
      (node (ref "U$13") (pin "B-") (pinfunction "B-_B-") (pintype "bidirectional"))
    )
    (net (code "15") (name "Net-(B$14-PadP$1)") (class "Default")
      (node (ref "B$14") (pin "P$1") (pinfunction "P$1_P$1") (pintype "bidirectional"))
      (node (ref "U$14") (pin "B-") (pinfunction "B-_B-") (pintype "bidirectional"))
    )
    (net (code "16") (name "Net-(B$15-PadP$1)") (class "Default")
      (node (ref "B$15") (pin "P$1") (pinfunction "P$1_P$1") (pintype "bidirectional"))
      (node (ref "U$15") (pin "B-") (pinfunction "B-_B-") (pintype "bidirectional"))
    )
    (net (code "17") (name "Net-(B$16-PadP$1)") (class "Default")
      (node (ref "B$16") (pin "P$1") (pinfunction "P$1_P$1") (pintype "bidirectional"))
      (node (ref "U$16") (pin "B-") (pinfunction "B-_B-") (pintype "bidirectional"))
    )
    (net (code "18") (name "Net-(B$17-PadP$1)") (class "Default")
      (node (ref "B$17") (pin "P$1") (pinfunction "P$1_P$1") (pintype "bidirectional"))
      (node (ref "U$17") (pin "B-") (pinfunction "B-_B-") (pintype "bidirectional"))
    )
    (net (code "19") (name "Net-(B$18-PadP$1)") (class "Default")
      (node (ref "B$18") (pin "P$1") (pinfunction "P$1_P$1") (pintype "bidirectional"))
      (node (ref "U$18") (pin "B-") (pinfunction "B-_B-") (pintype "bidirectional"))
    )
    (net (code "20") (name "Net-(B$19-PadP$1)") (class "Default")
      (node (ref "B$19") (pin "P$1") (pinfunction "P$1_P$1") (pintype "bidirectional"))
      (node (ref "U$19") (pin "B-") (pinfunction "B-_B-") (pintype "bidirectional"))
    )
    (net (code "21") (name "Net-(B$20-PadP$1)") (class "Default")
      (node (ref "B$20") (pin "P$1") (pinfunction "P$1_P$1") (pintype "bidirectional"))
      (node (ref "U$20") (pin "B-") (pinfunction "B-_B-") (pintype "bidirectional"))
    )
    (net (code "22") (name "Net-(B$21-PadP$1)") (class "Default")
      (node (ref "B$21") (pin "P$1") (pinfunction "P$1_P$1") (pintype "bidirectional"))
      (node (ref "U$21") (pin "B-") (pinfunction "B-_B-") (pintype "bidirectional"))
    )
    (net (code "23") (name "Net-(B$22-PadP$1)") (class "Default")
      (node (ref "B$22") (pin "P$1") (pinfunction "P$1_P$1") (pintype "bidirectional"))
      (node (ref "U$22") (pin "B-") (pinfunction "B-_B-") (pintype "bidirectional"))
    )
    (net (code "24") (name "Net-(B$23-PadP$1)") (class "Default")
      (node (ref "B$23") (pin "P$1") (pinfunction "P$1_P$1") (pintype "bidirectional"))
      (node (ref "U$23") (pin "B-") (pinfunction "B-_B-") (pintype "bidirectional"))
    )
    (net (code "25") (name "Net-(B$24-PadP$1)") (class "Default")
      (node (ref "B$24") (pin "P$1") (pinfunction "P$1_P$1") (pintype "bidirectional"))
      (node (ref "U$24") (pin "B-") (pinfunction "B-_B-") (pintype "bidirectional"))
    )
    (net (code "26") (name "Net-(B$25-PadP$1)") (class "Default")
      (node (ref "B$25") (pin "P$1") (pinfunction "P$1_P$1") (pintype "bidirectional"))
      (node (ref "U$25") (pin "B-") (pinfunction "B-_B-") (pintype "bidirectional"))
    )
    (net (code "27") (name "Net-(B$26-PadP$1)") (class "Default")
      (node (ref "B$26") (pin "P$1") (pinfunction "P$1_P$1") (pintype "bidirectional"))
      (node (ref "U$26") (pin "B-") (pinfunction "B-_B-") (pintype "bidirectional"))
    )
    (net (code "28") (name "Net-(B$27-PadP$1)") (class "Default")
      (node (ref "B$27") (pin "P$1") (pinfunction "P$1_P$1") (pintype "bidirectional"))
      (node (ref "U$27") (pin "B-") (pinfunction "B-_B-") (pintype "bidirectional"))
    )
    (net (code "29") (name "Net-(B$28-PadP$1)") (class "Default")
      (node (ref "B$28") (pin "P$1") (pinfunction "P$1_P$1") (pintype "bidirectional"))
      (node (ref "U$28") (pin "B-") (pinfunction "B-_B-") (pintype "bidirectional"))
    )
    (net (code "30") (name "Net-(B$29-PadP$1)") (class "Default")
      (node (ref "B$29") (pin "P$1") (pinfunction "P$1_P$1") (pintype "bidirectional"))
      (node (ref "U$29") (pin "B-") (pinfunction "B-_B-") (pintype "bidirectional"))
    )
    (net (code "31") (name "Net-(B$30-PadP$1)") (class "Default")
      (node (ref "B$30") (pin "P$1") (pinfunction "P$1_P$1") (pintype "bidirectional"))
      (node (ref "U$30") (pin "B-") (pinfunction "B-_B-") (pintype "bidirectional"))
    )
    (net (code "32") (name "Net-(B$31-PadP$1)") (class "Default")
      (node (ref "B$31") (pin "P$1") (pinfunction "P$1_P$1") (pintype "bidirectional"))
      (node (ref "U$31") (pin "B-") (pinfunction "B-_B-") (pintype "bidirectional"))
    )
    (net (code "33") (name "Net-(B$32-PadP$1)") (class "Default")
      (node (ref "B$32") (pin "P$1") (pinfunction "P$1_P$1") (pintype "bidirectional"))
      (node (ref "U$32") (pin "B-") (pinfunction "B-_B-") (pintype "bidirectional"))
    )
    (net (code "34") (name "Net-(B$33-PadP$1)") (class "Default")
      (node (ref "B$33") (pin "P$1") (pinfunction "P$1_P$1") (pintype "bidirectional"))
      (node (ref "U$33") (pin "B-") (pinfunction "B-_B-") (pintype "bidirectional"))
    )
    (net (code "35") (name "Net-(B$34-PadP$1)") (class "Default")
      (node (ref "B$34") (pin "P$1") (pinfunction "P$1_P$1") (pintype "bidirectional"))
      (node (ref "U$34") (pin "B-") (pinfunction "B-_B-") (pintype "bidirectional"))
    )
    (net (code "36") (name "Net-(B$35-PadP$1)") (class "Default")
      (node (ref "B$35") (pin "P$1") (pinfunction "P$1_P$1") (pintype "bidirectional"))
      (node (ref "U$35") (pin "B-") (pinfunction "B-_B-") (pintype "bidirectional"))
    )
    (net (code "37") (name "Net-(B$36-PadP$1)") (class "Default")
      (node (ref "B$36") (pin "P$1") (pinfunction "P$1_P$1") (pintype "bidirectional"))
      (node (ref "U$36") (pin "B-") (pinfunction "B-_B-") (pintype "bidirectional"))
    )
    (net (code "38") (name "Net-(B$37-PadP$1)") (class "Default")
      (node (ref "B$37") (pin "P$1") (pinfunction "P$1_P$1") (pintype "bidirectional"))
      (node (ref "U$37") (pin "B-") (pinfunction "B-_B-") (pintype "bidirectional"))
    )
    (net (code "39") (name "Net-(B$38-PadP$1)") (class "Default")
      (node (ref "B$38") (pin "P$1") (pinfunction "P$1_P$1") (pintype "bidirectional"))
      (node (ref "U$38") (pin "B-") (pinfunction "B-_B-") (pintype "bidirectional"))
    )
    (net (code "40") (name "Net-(B$39-PadP$1)") (class "Default")
      (node (ref "B$39") (pin "P$1") (pinfunction "P$1_P$1") (pintype "bidirectional"))
      (node (ref "U$39") (pin "B-") (pinfunction "B-_B-") (pintype "bidirectional"))
    )
    (net (code "41") (name "Net-(B$40-PadP$1)") (class "Default")
      (node (ref "B$40") (pin "P$1") (pinfunction "P$1_P$1") (pintype "bidirectional"))
      (node (ref "U$40") (pin "B-") (pinfunction "B-_B-") (pintype "bidirectional"))
    )
    (net (code "42") (name "Net-(B$41-PadP$1)") (class "Default")
      (node (ref "B$41") (pin "P$1") (pinfunction "P$1_P$1") (pintype "bidirectional"))
      (node (ref "U$41") (pin "B-") (pinfunction "B-_B-") (pintype "bidirectional"))
    )
    (net (code "43") (name "Net-(B$42-PadP$1)") (class "Default")
      (node (ref "B$42") (pin "P$1") (pinfunction "P$1_P$1") (pintype "bidirectional"))
      (node (ref "U$42") (pin "B-") (pinfunction "B-_B-") (pintype "bidirectional"))
    )
    (net (code "44") (name "Net-(B$43-PadP$1)") (class "Default")
      (node (ref "B$43") (pin "P$1") (pinfunction "P$1_P$1") (pintype "bidirectional"))
      (node (ref "U$43") (pin "B-") (pinfunction "B-_B-") (pintype "bidirectional"))
    )
    (net (code "45") (name "Net-(B$44-PadP$1)") (class "Default")
      (node (ref "B$44") (pin "P$1") (pinfunction "P$1_P$1") (pintype "bidirectional"))
      (node (ref "U$44") (pin "B-") (pinfunction "B-_B-") (pintype "bidirectional"))
    )
    (net (code "46") (name "Net-(B$45-PadP$1)") (class "Default")
      (node (ref "B$45") (pin "P$1") (pinfunction "P$1_P$1") (pintype "bidirectional"))
      (node (ref "U$45") (pin "B-") (pinfunction "B-_B-") (pintype "bidirectional"))
    )
    (net (code "47") (name "Net-(B$46-PadP$1)") (class "Default")
      (node (ref "B$46") (pin "P$1") (pinfunction "P$1_P$1") (pintype "bidirectional"))
      (node (ref "U$46") (pin "B-") (pinfunction "B-_B-") (pintype "bidirectional"))
    )
    (net (code "48") (name "Net-(B$47-PadP$1)") (class "Default")
      (node (ref "B$47") (pin "P$1") (pinfunction "P$1_P$1") (pintype "bidirectional"))
      (node (ref "U$47") (pin "B-") (pinfunction "B-_B-") (pintype "bidirectional"))
    )
    (net (code "49") (name "Net-(B$48-PadP$1)") (class "Default")
      (node (ref "B$48") (pin "P$1") (pinfunction "P$1_P$1") (pintype "bidirectional"))
      (node (ref "U$48") (pin "B-") (pinfunction "B-_B-") (pintype "bidirectional"))
    )
    (net (code "50") (name "Net-(B$49-PadP$1)") (class "Default")
      (node (ref "B$49") (pin "P$1") (pinfunction "P$1_P$1") (pintype "bidirectional"))
      (node (ref "U$49") (pin "B-") (pinfunction "B-_B-") (pintype "bidirectional"))
    )
    (net (code "51") (name "Net-(B$50-PadP$1)") (class "Default")
      (node (ref "B$50") (pin "P$1") (pinfunction "P$1_P$1") (pintype "bidirectional"))
      (node (ref "U$50") (pin "B-") (pinfunction "B-_B-") (pintype "bidirectional"))
    )
    (net (code "52") (name "Net-(B$51-PadP$1)") (class "Default")
      (node (ref "B$51") (pin "P$1") (pinfunction "P$1_P$1") (pintype "bidirectional"))
      (node (ref "U$51") (pin "B-") (pinfunction "B-_B-") (pintype "bidirectional"))
    )
    (net (code "53") (name "Net-(B$52-PadP$1)") (class "Default")
      (node (ref "B$52") (pin "P$1") (pinfunction "P$1_P$1") (pintype "bidirectional"))
      (node (ref "U$52") (pin "B-") (pinfunction "B-_B-") (pintype "bidirectional"))
    )
    (net (code "54") (name "Net-(B$53-PadP$1)") (class "Default")
      (node (ref "B$53") (pin "P$1") (pinfunction "P$1_P$1") (pintype "bidirectional"))
      (node (ref "U$53") (pin "B-") (pinfunction "B-_B-") (pintype "bidirectional"))
    )
    (net (code "55") (name "Net-(B$54-PadP$1)") (class "Default")
      (node (ref "B$54") (pin "P$1") (pinfunction "P$1_P$1") (pintype "bidirectional"))
      (node (ref "U$54") (pin "B-") (pinfunction "B-_B-") (pintype "bidirectional"))
    )
    (net (code "56") (name "Net-(B$55-PadP$1)") (class "Default")
      (node (ref "B$55") (pin "P$1") (pinfunction "P$1_P$1") (pintype "bidirectional"))
      (node (ref "U$55") (pin "B-") (pinfunction "B-_B-") (pintype "bidirectional"))
    )
    (net (code "57") (name "Net-(B$56-PadP$1)") (class "Default")
      (node (ref "B$56") (pin "P$1") (pinfunction "P$1_P$1") (pintype "bidirectional"))
      (node (ref "U$56") (pin "B-") (pinfunction "B-_B-") (pintype "bidirectional"))
    )
    (net (code "58") (name "Net-(B$57-PadP$1)") (class "Default")
      (node (ref "B$57") (pin "P$1") (pinfunction "P$1_P$1") (pintype "bidirectional"))
      (node (ref "U$57") (pin "B-") (pinfunction "B-_B-") (pintype "bidirectional"))
    )
    (net (code "59") (name "Net-(B$58-PadP$1)") (class "Default")
      (node (ref "B$58") (pin "P$1") (pinfunction "P$1_P$1") (pintype "bidirectional"))
      (node (ref "U$58") (pin "B-") (pinfunction "B-_B-") (pintype "bidirectional"))
    )
    (net (code "60") (name "Net-(B$59-PadP$1)") (class "Default")
      (node (ref "B$59") (pin "P$1") (pinfunction "P$1_P$1") (pintype "bidirectional"))
      (node (ref "U$59") (pin "B-") (pinfunction "B-_B-") (pintype "bidirectional"))
    )
    (net (code "61") (name "Net-(B$60-PadP$1)") (class "Default")
      (node (ref "B$60") (pin "P$1") (pinfunction "P$1_P$1") (pintype "bidirectional"))
      (node (ref "U$60") (pin "B-") (pinfunction "B-_B-") (pintype "bidirectional"))
    )
    (net (code "62") (name "Net-(B$61-PadP$1)") (class "Default")
      (node (ref "B$61") (pin "P$1") (pinfunction "P$1_P$1") (pintype "bidirectional"))
      (node (ref "U$61") (pin "B-") (pinfunction "B-_B-") (pintype "bidirectional"))
    )
    (net (code "63") (name "Net-(B$62-PadP$1)") (class "Default")
      (node (ref "B$62") (pin "P$1") (pinfunction "P$1_P$1") (pintype "bidirectional"))
      (node (ref "U$62") (pin "B-") (pinfunction "B-_B-") (pintype "bidirectional"))
    )
    (net (code "64") (name "Net-(B$63-PadP$1)") (class "Default")
      (node (ref "B$63") (pin "P$1") (pinfunction "P$1_P$1") (pintype "bidirectional"))
      (node (ref "U$63") (pin "B-") (pinfunction "B-_B-") (pintype "bidirectional"))
    )
    (net (code "65") (name "Net-(B$64-PadP$1)") (class "Default")
      (node (ref "B$64") (pin "P$1") (pinfunction "P$1_P$1") (pintype "bidirectional"))
      (node (ref "U$64") (pin "B-") (pinfunction "B-_B-") (pintype "bidirectional"))
    )
    (net (code "66") (name "Net-(G$1-PadP$1)") (class "Default")
      (node (ref "G$1") (pin "P$1") (pinfunction "P$1_P$1") (pintype "bidirectional"))
      (node (ref "U$1") (pin "G-") (pinfunction "G-_G-") (pintype "bidirectional"))
    )
    (net (code "67") (name "Net-(G$2-PadP$1)") (class "Default")
      (node (ref "G$2") (pin "P$1") (pinfunction "P$1_P$1") (pintype "bidirectional"))
      (node (ref "U$2") (pin "G-") (pinfunction "G-_G-") (pintype "bidirectional"))
    )
    (net (code "68") (name "Net-(G$3-PadP$1)") (class "Default")
      (node (ref "G$3") (pin "P$1") (pinfunction "P$1_P$1") (pintype "bidirectional"))
      (node (ref "U$3") (pin "G-") (pinfunction "G-_G-") (pintype "bidirectional"))
    )
    (net (code "69") (name "Net-(G$4-PadP$1)") (class "Default")
      (node (ref "G$4") (pin "P$1") (pinfunction "P$1_P$1") (pintype "bidirectional"))
      (node (ref "U$4") (pin "G-") (pinfunction "G-_G-") (pintype "bidirectional"))
    )
    (net (code "70") (name "Net-(G$5-PadP$1)") (class "Default")
      (node (ref "G$5") (pin "P$1") (pinfunction "P$1_P$1") (pintype "bidirectional"))
      (node (ref "U$5") (pin "G-") (pinfunction "G-_G-") (pintype "bidirectional"))
    )
    (net (code "71") (name "Net-(G$6-PadP$1)") (class "Default")
      (node (ref "G$6") (pin "P$1") (pinfunction "P$1_P$1") (pintype "bidirectional"))
      (node (ref "U$6") (pin "G-") (pinfunction "G-_G-") (pintype "bidirectional"))
    )
    (net (code "72") (name "Net-(G$7-PadP$1)") (class "Default")
      (node (ref "G$7") (pin "P$1") (pinfunction "P$1_P$1") (pintype "bidirectional"))
      (node (ref "U$7") (pin "G-") (pinfunction "G-_G-") (pintype "bidirectional"))
    )
    (net (code "73") (name "Net-(G$8-PadP$1)") (class "Default")
      (node (ref "G$8") (pin "P$1") (pinfunction "P$1_P$1") (pintype "bidirectional"))
      (node (ref "U$8") (pin "G-") (pinfunction "G-_G-") (pintype "bidirectional"))
    )
    (net (code "74") (name "Net-(G$9-PadP$1)") (class "Default")
      (node (ref "G$9") (pin "P$1") (pinfunction "P$1_P$1") (pintype "bidirectional"))
      (node (ref "U$9") (pin "G-") (pinfunction "G-_G-") (pintype "bidirectional"))
    )
    (net (code "75") (name "Net-(G$10-PadP$1)") (class "Default")
      (node (ref "G$10") (pin "P$1") (pinfunction "P$1_P$1") (pintype "bidirectional"))
      (node (ref "U$10") (pin "G-") (pinfunction "G-_G-") (pintype "bidirectional"))
    )
    (net (code "76") (name "Net-(G$11-PadP$1)") (class "Default")
      (node (ref "G$11") (pin "P$1") (pinfunction "P$1_P$1") (pintype "bidirectional"))
      (node (ref "U$11") (pin "G-") (pinfunction "G-_G-") (pintype "bidirectional"))
    )
    (net (code "77") (name "Net-(G$12-PadP$1)") (class "Default")
      (node (ref "G$12") (pin "P$1") (pinfunction "P$1_P$1") (pintype "bidirectional"))
      (node (ref "U$12") (pin "G-") (pinfunction "G-_G-") (pintype "bidirectional"))
    )
    (net (code "78") (name "Net-(G$13-PadP$1)") (class "Default")
      (node (ref "G$13") (pin "P$1") (pinfunction "P$1_P$1") (pintype "bidirectional"))
      (node (ref "U$13") (pin "G-") (pinfunction "G-_G-") (pintype "bidirectional"))
    )
    (net (code "79") (name "Net-(G$14-PadP$1)") (class "Default")
      (node (ref "G$14") (pin "P$1") (pinfunction "P$1_P$1") (pintype "bidirectional"))
      (node (ref "U$14") (pin "G-") (pinfunction "G-_G-") (pintype "bidirectional"))
    )
    (net (code "80") (name "Net-(G$15-PadP$1)") (class "Default")
      (node (ref "G$15") (pin "P$1") (pinfunction "P$1_P$1") (pintype "bidirectional"))
      (node (ref "U$15") (pin "G-") (pinfunction "G-_G-") (pintype "bidirectional"))
    )
    (net (code "81") (name "Net-(G$16-PadP$1)") (class "Default")
      (node (ref "G$16") (pin "P$1") (pinfunction "P$1_P$1") (pintype "bidirectional"))
      (node (ref "U$16") (pin "G-") (pinfunction "G-_G-") (pintype "bidirectional"))
    )
    (net (code "82") (name "Net-(G$17-PadP$1)") (class "Default")
      (node (ref "G$17") (pin "P$1") (pinfunction "P$1_P$1") (pintype "bidirectional"))
      (node (ref "U$17") (pin "G-") (pinfunction "G-_G-") (pintype "bidirectional"))
    )
    (net (code "83") (name "Net-(G$18-PadP$1)") (class "Default")
      (node (ref "G$18") (pin "P$1") (pinfunction "P$1_P$1") (pintype "bidirectional"))
      (node (ref "U$18") (pin "G-") (pinfunction "G-_G-") (pintype "bidirectional"))
    )
    (net (code "84") (name "Net-(G$19-PadP$1)") (class "Default")
      (node (ref "G$19") (pin "P$1") (pinfunction "P$1_P$1") (pintype "bidirectional"))
      (node (ref "U$19") (pin "G-") (pinfunction "G-_G-") (pintype "bidirectional"))
    )
    (net (code "85") (name "Net-(G$20-PadP$1)") (class "Default")
      (node (ref "G$20") (pin "P$1") (pinfunction "P$1_P$1") (pintype "bidirectional"))
      (node (ref "U$20") (pin "G-") (pinfunction "G-_G-") (pintype "bidirectional"))
    )
    (net (code "86") (name "Net-(G$21-PadP$1)") (class "Default")
      (node (ref "G$21") (pin "P$1") (pinfunction "P$1_P$1") (pintype "bidirectional"))
      (node (ref "U$21") (pin "G-") (pinfunction "G-_G-") (pintype "bidirectional"))
    )
    (net (code "87") (name "Net-(G$22-PadP$1)") (class "Default")
      (node (ref "G$22") (pin "P$1") (pinfunction "P$1_P$1") (pintype "bidirectional"))
      (node (ref "U$22") (pin "G-") (pinfunction "G-_G-") (pintype "bidirectional"))
    )
    (net (code "88") (name "Net-(G$23-PadP$1)") (class "Default")
      (node (ref "G$23") (pin "P$1") (pinfunction "P$1_P$1") (pintype "bidirectional"))
      (node (ref "U$23") (pin "G-") (pinfunction "G-_G-") (pintype "bidirectional"))
    )
    (net (code "89") (name "Net-(G$24-PadP$1)") (class "Default")
      (node (ref "G$24") (pin "P$1") (pinfunction "P$1_P$1") (pintype "bidirectional"))
      (node (ref "U$24") (pin "G-") (pinfunction "G-_G-") (pintype "bidirectional"))
    )
    (net (code "90") (name "Net-(G$25-PadP$1)") (class "Default")
      (node (ref "G$25") (pin "P$1") (pinfunction "P$1_P$1") (pintype "bidirectional"))
      (node (ref "U$25") (pin "G-") (pinfunction "G-_G-") (pintype "bidirectional"))
    )
    (net (code "91") (name "Net-(G$26-PadP$1)") (class "Default")
      (node (ref "G$26") (pin "P$1") (pinfunction "P$1_P$1") (pintype "bidirectional"))
      (node (ref "U$26") (pin "G-") (pinfunction "G-_G-") (pintype "bidirectional"))
    )
    (net (code "92") (name "Net-(G$27-PadP$1)") (class "Default")
      (node (ref "G$27") (pin "P$1") (pinfunction "P$1_P$1") (pintype "bidirectional"))
      (node (ref "U$27") (pin "G-") (pinfunction "G-_G-") (pintype "bidirectional"))
    )
    (net (code "93") (name "Net-(G$28-PadP$1)") (class "Default")
      (node (ref "G$28") (pin "P$1") (pinfunction "P$1_P$1") (pintype "bidirectional"))
      (node (ref "U$28") (pin "G-") (pinfunction "G-_G-") (pintype "bidirectional"))
    )
    (net (code "94") (name "Net-(G$29-PadP$1)") (class "Default")
      (node (ref "G$29") (pin "P$1") (pinfunction "P$1_P$1") (pintype "bidirectional"))
      (node (ref "U$29") (pin "G-") (pinfunction "G-_G-") (pintype "bidirectional"))
    )
    (net (code "95") (name "Net-(G$30-PadP$1)") (class "Default")
      (node (ref "G$30") (pin "P$1") (pinfunction "P$1_P$1") (pintype "bidirectional"))
      (node (ref "U$30") (pin "G-") (pinfunction "G-_G-") (pintype "bidirectional"))
    )
    (net (code "96") (name "Net-(G$31-PadP$1)") (class "Default")
      (node (ref "G$31") (pin "P$1") (pinfunction "P$1_P$1") (pintype "bidirectional"))
      (node (ref "U$31") (pin "G-") (pinfunction "G-_G-") (pintype "bidirectional"))
    )
    (net (code "97") (name "Net-(G$32-PadP$1)") (class "Default")
      (node (ref "G$32") (pin "P$1") (pinfunction "P$1_P$1") (pintype "bidirectional"))
      (node (ref "U$32") (pin "G-") (pinfunction "G-_G-") (pintype "bidirectional"))
    )
    (net (code "98") (name "Net-(G$33-PadP$1)") (class "Default")
      (node (ref "G$33") (pin "P$1") (pinfunction "P$1_P$1") (pintype "bidirectional"))
      (node (ref "U$33") (pin "G-") (pinfunction "G-_G-") (pintype "bidirectional"))
    )
    (net (code "99") (name "Net-(G$34-PadP$1)") (class "Default")
      (node (ref "G$34") (pin "P$1") (pinfunction "P$1_P$1") (pintype "bidirectional"))
      (node (ref "U$34") (pin "G-") (pinfunction "G-_G-") (pintype "bidirectional"))
    )
    (net (code "100") (name "Net-(G$35-PadP$1)") (class "Default")
      (node (ref "G$35") (pin "P$1") (pinfunction "P$1_P$1") (pintype "bidirectional"))
      (node (ref "U$35") (pin "G-") (pinfunction "G-_G-") (pintype "bidirectional"))
    )
    (net (code "101") (name "Net-(G$36-PadP$1)") (class "Default")
      (node (ref "G$36") (pin "P$1") (pinfunction "P$1_P$1") (pintype "bidirectional"))
      (node (ref "U$36") (pin "G-") (pinfunction "G-_G-") (pintype "bidirectional"))
    )
    (net (code "102") (name "Net-(G$37-PadP$1)") (class "Default")
      (node (ref "G$37") (pin "P$1") (pinfunction "P$1_P$1") (pintype "bidirectional"))
      (node (ref "U$37") (pin "G-") (pinfunction "G-_G-") (pintype "bidirectional"))
    )
    (net (code "103") (name "Net-(G$38-PadP$1)") (class "Default")
      (node (ref "G$38") (pin "P$1") (pinfunction "P$1_P$1") (pintype "bidirectional"))
      (node (ref "U$38") (pin "G-") (pinfunction "G-_G-") (pintype "bidirectional"))
    )
    (net (code "104") (name "Net-(G$39-PadP$1)") (class "Default")
      (node (ref "G$39") (pin "P$1") (pinfunction "P$1_P$1") (pintype "bidirectional"))
      (node (ref "U$39") (pin "G-") (pinfunction "G-_G-") (pintype "bidirectional"))
    )
    (net (code "105") (name "Net-(G$40-PadP$1)") (class "Default")
      (node (ref "G$40") (pin "P$1") (pinfunction "P$1_P$1") (pintype "bidirectional"))
      (node (ref "U$40") (pin "G-") (pinfunction "G-_G-") (pintype "bidirectional"))
    )
    (net (code "106") (name "Net-(G$41-PadP$1)") (class "Default")
      (node (ref "G$41") (pin "P$1") (pinfunction "P$1_P$1") (pintype "bidirectional"))
      (node (ref "U$41") (pin "G-") (pinfunction "G-_G-") (pintype "bidirectional"))
    )
    (net (code "107") (name "Net-(G$42-PadP$1)") (class "Default")
      (node (ref "G$42") (pin "P$1") (pinfunction "P$1_P$1") (pintype "bidirectional"))
      (node (ref "U$42") (pin "G-") (pinfunction "G-_G-") (pintype "bidirectional"))
    )
    (net (code "108") (name "Net-(G$43-PadP$1)") (class "Default")
      (node (ref "G$43") (pin "P$1") (pinfunction "P$1_P$1") (pintype "bidirectional"))
      (node (ref "U$43") (pin "G-") (pinfunction "G-_G-") (pintype "bidirectional"))
    )
    (net (code "109") (name "Net-(G$44-PadP$1)") (class "Default")
      (node (ref "G$44") (pin "P$1") (pinfunction "P$1_P$1") (pintype "bidirectional"))
      (node (ref "U$44") (pin "G-") (pinfunction "G-_G-") (pintype "bidirectional"))
    )
    (net (code "110") (name "Net-(G$45-PadP$1)") (class "Default")
      (node (ref "G$45") (pin "P$1") (pinfunction "P$1_P$1") (pintype "bidirectional"))
      (node (ref "U$45") (pin "G-") (pinfunction "G-_G-") (pintype "bidirectional"))
    )
    (net (code "111") (name "Net-(G$46-PadP$1)") (class "Default")
      (node (ref "G$46") (pin "P$1") (pinfunction "P$1_P$1") (pintype "bidirectional"))
      (node (ref "U$46") (pin "G-") (pinfunction "G-_G-") (pintype "bidirectional"))
    )
    (net (code "112") (name "Net-(G$47-PadP$1)") (class "Default")
      (node (ref "G$47") (pin "P$1") (pinfunction "P$1_P$1") (pintype "bidirectional"))
      (node (ref "U$47") (pin "G-") (pinfunction "G-_G-") (pintype "bidirectional"))
    )
    (net (code "113") (name "Net-(G$48-PadP$1)") (class "Default")
      (node (ref "G$48") (pin "P$1") (pinfunction "P$1_P$1") (pintype "bidirectional"))
      (node (ref "U$48") (pin "G-") (pinfunction "G-_G-") (pintype "bidirectional"))
    )
    (net (code "114") (name "Net-(G$49-PadP$1)") (class "Default")
      (node (ref "G$49") (pin "P$1") (pinfunction "P$1_P$1") (pintype "bidirectional"))
      (node (ref "U$49") (pin "G-") (pinfunction "G-_G-") (pintype "bidirectional"))
    )
    (net (code "115") (name "Net-(G$50-PadP$1)") (class "Default")
      (node (ref "G$50") (pin "P$1") (pinfunction "P$1_P$1") (pintype "bidirectional"))
      (node (ref "U$50") (pin "G-") (pinfunction "G-_G-") (pintype "bidirectional"))
    )
    (net (code "116") (name "Net-(G$51-PadP$1)") (class "Default")
      (node (ref "G$51") (pin "P$1") (pinfunction "P$1_P$1") (pintype "bidirectional"))
      (node (ref "U$51") (pin "G-") (pinfunction "G-_G-") (pintype "bidirectional"))
    )
    (net (code "117") (name "Net-(G$52-PadP$1)") (class "Default")
      (node (ref "G$52") (pin "P$1") (pinfunction "P$1_P$1") (pintype "bidirectional"))
      (node (ref "U$52") (pin "G-") (pinfunction "G-_G-") (pintype "bidirectional"))
    )
    (net (code "118") (name "Net-(G$53-PadP$1)") (class "Default")
      (node (ref "G$53") (pin "P$1") (pinfunction "P$1_P$1") (pintype "bidirectional"))
      (node (ref "U$53") (pin "G-") (pinfunction "G-_G-") (pintype "bidirectional"))
    )
    (net (code "119") (name "Net-(G$54-PadP$1)") (class "Default")
      (node (ref "G$54") (pin "P$1") (pinfunction "P$1_P$1") (pintype "bidirectional"))
      (node (ref "U$54") (pin "G-") (pinfunction "G-_G-") (pintype "bidirectional"))
    )
    (net (code "120") (name "Net-(G$55-PadP$1)") (class "Default")
      (node (ref "G$55") (pin "P$1") (pinfunction "P$1_P$1") (pintype "bidirectional"))
      (node (ref "U$55") (pin "G-") (pinfunction "G-_G-") (pintype "bidirectional"))
    )
    (net (code "121") (name "Net-(G$56-PadP$1)") (class "Default")
      (node (ref "G$56") (pin "P$1") (pinfunction "P$1_P$1") (pintype "bidirectional"))
      (node (ref "U$56") (pin "G-") (pinfunction "G-_G-") (pintype "bidirectional"))
    )
    (net (code "122") (name "Net-(G$57-PadP$1)") (class "Default")
      (node (ref "G$57") (pin "P$1") (pinfunction "P$1_P$1") (pintype "bidirectional"))
      (node (ref "U$57") (pin "G-") (pinfunction "G-_G-") (pintype "bidirectional"))
    )
    (net (code "123") (name "Net-(G$58-PadP$1)") (class "Default")
      (node (ref "G$58") (pin "P$1") (pinfunction "P$1_P$1") (pintype "bidirectional"))
      (node (ref "U$58") (pin "G-") (pinfunction "G-_G-") (pintype "bidirectional"))
    )
    (net (code "124") (name "Net-(G$59-PadP$1)") (class "Default")
      (node (ref "G$59") (pin "P$1") (pinfunction "P$1_P$1") (pintype "bidirectional"))
      (node (ref "U$59") (pin "G-") (pinfunction "G-_G-") (pintype "bidirectional"))
    )
    (net (code "125") (name "Net-(G$60-PadP$1)") (class "Default")
      (node (ref "G$60") (pin "P$1") (pinfunction "P$1_P$1") (pintype "bidirectional"))
      (node (ref "U$60") (pin "G-") (pinfunction "G-_G-") (pintype "bidirectional"))
    )
    (net (code "126") (name "Net-(G$61-PadP$1)") (class "Default")
      (node (ref "G$61") (pin "P$1") (pinfunction "P$1_P$1") (pintype "bidirectional"))
      (node (ref "U$61") (pin "G-") (pinfunction "G-_G-") (pintype "bidirectional"))
    )
    (net (code "127") (name "Net-(G$62-PadP$1)") (class "Default")
      (node (ref "G$62") (pin "P$1") (pinfunction "P$1_P$1") (pintype "bidirectional"))
      (node (ref "U$62") (pin "G-") (pinfunction "G-_G-") (pintype "bidirectional"))
    )
    (net (code "128") (name "Net-(G$63-PadP$1)") (class "Default")
      (node (ref "G$63") (pin "P$1") (pinfunction "P$1_P$1") (pintype "bidirectional"))
      (node (ref "U$63") (pin "G-") (pinfunction "G-_G-") (pintype "bidirectional"))
    )
    (net (code "129") (name "Net-(G$64-PadP$1)") (class "Default")
      (node (ref "G$64") (pin "P$1") (pinfunction "P$1_P$1") (pintype "bidirectional"))
      (node (ref "U$64") (pin "G-") (pinfunction "G-_G-") (pintype "bidirectional"))
    )
    (net (code "130") (name "Net-(R$1-PadP$1)") (class "Default")
      (node (ref "R$1") (pin "P$1") (pinfunction "P$1_P$1") (pintype "bidirectional"))
      (node (ref "U$1") (pin "R-") (pinfunction "R-_R-") (pintype "bidirectional"))
    )
    (net (code "131") (name "Net-(R$2-PadP$1)") (class "Default")
      (node (ref "R$2") (pin "P$1") (pinfunction "P$1_P$1") (pintype "bidirectional"))
      (node (ref "U$2") (pin "R-") (pinfunction "R-_R-") (pintype "bidirectional"))
    )
    (net (code "132") (name "Net-(R$3-PadP$1)") (class "Default")
      (node (ref "R$3") (pin "P$1") (pinfunction "P$1_P$1") (pintype "bidirectional"))
      (node (ref "U$3") (pin "R-") (pinfunction "R-_R-") (pintype "bidirectional"))
    )
    (net (code "133") (name "Net-(R$4-PadP$1)") (class "Default")
      (node (ref "R$4") (pin "P$1") (pinfunction "P$1_P$1") (pintype "bidirectional"))
      (node (ref "U$4") (pin "R-") (pinfunction "R-_R-") (pintype "bidirectional"))
    )
    (net (code "134") (name "Net-(R$5-PadP$1)") (class "Default")
      (node (ref "R$5") (pin "P$1") (pinfunction "P$1_P$1") (pintype "bidirectional"))
      (node (ref "U$5") (pin "R-") (pinfunction "R-_R-") (pintype "bidirectional"))
    )
    (net (code "135") (name "Net-(R$6-PadP$1)") (class "Default")
      (node (ref "R$6") (pin "P$1") (pinfunction "P$1_P$1") (pintype "bidirectional"))
      (node (ref "U$6") (pin "R-") (pinfunction "R-_R-") (pintype "bidirectional"))
    )
    (net (code "136") (name "Net-(R$7-PadP$1)") (class "Default")
      (node (ref "R$7") (pin "P$1") (pinfunction "P$1_P$1") (pintype "bidirectional"))
      (node (ref "U$7") (pin "R-") (pinfunction "R-_R-") (pintype "bidirectional"))
    )
    (net (code "137") (name "Net-(R$8-PadP$1)") (class "Default")
      (node (ref "R$8") (pin "P$1") (pinfunction "P$1_P$1") (pintype "bidirectional"))
      (node (ref "U$8") (pin "R-") (pinfunction "R-_R-") (pintype "bidirectional"))
    )
    (net (code "138") (name "Net-(R$9-PadP$1)") (class "Default")
      (node (ref "R$9") (pin "P$1") (pinfunction "P$1_P$1") (pintype "bidirectional"))
      (node (ref "U$9") (pin "R-") (pinfunction "R-_R-") (pintype "bidirectional"))
    )
    (net (code "139") (name "Net-(R$10-PadP$1)") (class "Default")
      (node (ref "R$10") (pin "P$1") (pinfunction "P$1_P$1") (pintype "bidirectional"))
      (node (ref "U$10") (pin "R-") (pinfunction "R-_R-") (pintype "bidirectional"))
    )
    (net (code "140") (name "Net-(R$11-PadP$1)") (class "Default")
      (node (ref "R$11") (pin "P$1") (pinfunction "P$1_P$1") (pintype "bidirectional"))
      (node (ref "U$11") (pin "R-") (pinfunction "R-_R-") (pintype "bidirectional"))
    )
    (net (code "141") (name "Net-(R$12-PadP$1)") (class "Default")
      (node (ref "R$12") (pin "P$1") (pinfunction "P$1_P$1") (pintype "bidirectional"))
      (node (ref "U$12") (pin "R-") (pinfunction "R-_R-") (pintype "bidirectional"))
    )
    (net (code "142") (name "Net-(R$13-PadP$1)") (class "Default")
      (node (ref "R$13") (pin "P$1") (pinfunction "P$1_P$1") (pintype "bidirectional"))
      (node (ref "U$13") (pin "R-") (pinfunction "R-_R-") (pintype "bidirectional"))
    )
    (net (code "143") (name "Net-(R$14-PadP$1)") (class "Default")
      (node (ref "R$14") (pin "P$1") (pinfunction "P$1_P$1") (pintype "bidirectional"))
      (node (ref "U$14") (pin "R-") (pinfunction "R-_R-") (pintype "bidirectional"))
    )
    (net (code "144") (name "Net-(R$15-PadP$1)") (class "Default")
      (node (ref "R$15") (pin "P$1") (pinfunction "P$1_P$1") (pintype "bidirectional"))
      (node (ref "U$15") (pin "R-") (pinfunction "R-_R-") (pintype "bidirectional"))
    )
    (net (code "145") (name "Net-(R$16-PadP$1)") (class "Default")
      (node (ref "R$16") (pin "P$1") (pinfunction "P$1_P$1") (pintype "bidirectional"))
      (node (ref "U$16") (pin "R-") (pinfunction "R-_R-") (pintype "bidirectional"))
    )
    (net (code "146") (name "Net-(R$17-PadP$1)") (class "Default")
      (node (ref "R$17") (pin "P$1") (pinfunction "P$1_P$1") (pintype "bidirectional"))
      (node (ref "U$17") (pin "R-") (pinfunction "R-_R-") (pintype "bidirectional"))
    )
    (net (code "147") (name "Net-(R$18-PadP$1)") (class "Default")
      (node (ref "R$18") (pin "P$1") (pinfunction "P$1_P$1") (pintype "bidirectional"))
      (node (ref "U$18") (pin "R-") (pinfunction "R-_R-") (pintype "bidirectional"))
    )
    (net (code "148") (name "Net-(R$19-PadP$1)") (class "Default")
      (node (ref "R$19") (pin "P$1") (pinfunction "P$1_P$1") (pintype "bidirectional"))
      (node (ref "U$19") (pin "R-") (pinfunction "R-_R-") (pintype "bidirectional"))
    )
    (net (code "149") (name "Net-(R$20-PadP$1)") (class "Default")
      (node (ref "R$20") (pin "P$1") (pinfunction "P$1_P$1") (pintype "bidirectional"))
      (node (ref "U$20") (pin "R-") (pinfunction "R-_R-") (pintype "bidirectional"))
    )
    (net (code "150") (name "Net-(R$21-PadP$1)") (class "Default")
      (node (ref "R$21") (pin "P$1") (pinfunction "P$1_P$1") (pintype "bidirectional"))
      (node (ref "U$21") (pin "R-") (pinfunction "R-_R-") (pintype "bidirectional"))
    )
    (net (code "151") (name "Net-(R$22-PadP$1)") (class "Default")
      (node (ref "R$22") (pin "P$1") (pinfunction "P$1_P$1") (pintype "bidirectional"))
      (node (ref "U$22") (pin "R-") (pinfunction "R-_R-") (pintype "bidirectional"))
    )
    (net (code "152") (name "Net-(R$23-PadP$1)") (class "Default")
      (node (ref "R$23") (pin "P$1") (pinfunction "P$1_P$1") (pintype "bidirectional"))
      (node (ref "U$23") (pin "R-") (pinfunction "R-_R-") (pintype "bidirectional"))
    )
    (net (code "153") (name "Net-(R$24-PadP$1)") (class "Default")
      (node (ref "R$24") (pin "P$1") (pinfunction "P$1_P$1") (pintype "bidirectional"))
      (node (ref "U$24") (pin "R-") (pinfunction "R-_R-") (pintype "bidirectional"))
    )
    (net (code "154") (name "Net-(R$25-PadP$1)") (class "Default")
      (node (ref "R$25") (pin "P$1") (pinfunction "P$1_P$1") (pintype "bidirectional"))
      (node (ref "U$25") (pin "R-") (pinfunction "R-_R-") (pintype "bidirectional"))
    )
    (net (code "155") (name "Net-(R$26-PadP$1)") (class "Default")
      (node (ref "R$26") (pin "P$1") (pinfunction "P$1_P$1") (pintype "bidirectional"))
      (node (ref "U$26") (pin "R-") (pinfunction "R-_R-") (pintype "bidirectional"))
    )
    (net (code "156") (name "Net-(R$27-PadP$1)") (class "Default")
      (node (ref "R$27") (pin "P$1") (pinfunction "P$1_P$1") (pintype "bidirectional"))
      (node (ref "U$27") (pin "R-") (pinfunction "R-_R-") (pintype "bidirectional"))
    )
    (net (code "157") (name "Net-(R$28-PadP$1)") (class "Default")
      (node (ref "R$28") (pin "P$1") (pinfunction "P$1_P$1") (pintype "bidirectional"))
      (node (ref "U$28") (pin "R-") (pinfunction "R-_R-") (pintype "bidirectional"))
    )
    (net (code "158") (name "Net-(R$29-PadP$1)") (class "Default")
      (node (ref "R$29") (pin "P$1") (pinfunction "P$1_P$1") (pintype "bidirectional"))
      (node (ref "U$29") (pin "R-") (pinfunction "R-_R-") (pintype "bidirectional"))
    )
    (net (code "159") (name "Net-(R$30-PadP$1)") (class "Default")
      (node (ref "R$30") (pin "P$1") (pinfunction "P$1_P$1") (pintype "bidirectional"))
      (node (ref "U$30") (pin "R-") (pinfunction "R-_R-") (pintype "bidirectional"))
    )
    (net (code "160") (name "Net-(R$31-PadP$1)") (class "Default")
      (node (ref "R$31") (pin "P$1") (pinfunction "P$1_P$1") (pintype "bidirectional"))
      (node (ref "U$31") (pin "R-") (pinfunction "R-_R-") (pintype "bidirectional"))
    )
    (net (code "161") (name "Net-(R$32-PadP$1)") (class "Default")
      (node (ref "R$32") (pin "P$1") (pinfunction "P$1_P$1") (pintype "bidirectional"))
      (node (ref "U$32") (pin "R-") (pinfunction "R-_R-") (pintype "bidirectional"))
    )
    (net (code "162") (name "Net-(R$33-PadP$1)") (class "Default")
      (node (ref "R$33") (pin "P$1") (pinfunction "P$1_P$1") (pintype "bidirectional"))
      (node (ref "U$33") (pin "R-") (pinfunction "R-_R-") (pintype "bidirectional"))
    )
    (net (code "163") (name "Net-(R$34-PadP$1)") (class "Default")
      (node (ref "R$34") (pin "P$1") (pinfunction "P$1_P$1") (pintype "bidirectional"))
      (node (ref "U$34") (pin "R-") (pinfunction "R-_R-") (pintype "bidirectional"))
    )
    (net (code "164") (name "Net-(R$35-PadP$1)") (class "Default")
      (node (ref "R$35") (pin "P$1") (pinfunction "P$1_P$1") (pintype "bidirectional"))
      (node (ref "U$35") (pin "R-") (pinfunction "R-_R-") (pintype "bidirectional"))
    )
    (net (code "165") (name "Net-(R$36-PadP$1)") (class "Default")
      (node (ref "R$36") (pin "P$1") (pinfunction "P$1_P$1") (pintype "bidirectional"))
      (node (ref "U$36") (pin "R-") (pinfunction "R-_R-") (pintype "bidirectional"))
    )
    (net (code "166") (name "Net-(R$37-PadP$1)") (class "Default")
      (node (ref "R$37") (pin "P$1") (pinfunction "P$1_P$1") (pintype "bidirectional"))
      (node (ref "U$37") (pin "R-") (pinfunction "R-_R-") (pintype "bidirectional"))
    )
    (net (code "167") (name "Net-(R$38-PadP$1)") (class "Default")
      (node (ref "R$38") (pin "P$1") (pinfunction "P$1_P$1") (pintype "bidirectional"))
      (node (ref "U$38") (pin "R-") (pinfunction "R-_R-") (pintype "bidirectional"))
    )
    (net (code "168") (name "Net-(R$39-PadP$1)") (class "Default")
      (node (ref "R$39") (pin "P$1") (pinfunction "P$1_P$1") (pintype "bidirectional"))
      (node (ref "U$39") (pin "R-") (pinfunction "R-_R-") (pintype "bidirectional"))
    )
    (net (code "169") (name "Net-(R$40-PadP$1)") (class "Default")
      (node (ref "R$40") (pin "P$1") (pinfunction "P$1_P$1") (pintype "bidirectional"))
      (node (ref "U$40") (pin "R-") (pinfunction "R-_R-") (pintype "bidirectional"))
    )
    (net (code "170") (name "Net-(R$41-PadP$1)") (class "Default")
      (node (ref "R$41") (pin "P$1") (pinfunction "P$1_P$1") (pintype "bidirectional"))
      (node (ref "U$41") (pin "R-") (pinfunction "R-_R-") (pintype "bidirectional"))
    )
    (net (code "171") (name "Net-(R$42-PadP$1)") (class "Default")
      (node (ref "R$42") (pin "P$1") (pinfunction "P$1_P$1") (pintype "bidirectional"))
      (node (ref "U$42") (pin "R-") (pinfunction "R-_R-") (pintype "bidirectional"))
    )
    (net (code "172") (name "Net-(R$43-PadP$1)") (class "Default")
      (node (ref "R$43") (pin "P$1") (pinfunction "P$1_P$1") (pintype "bidirectional"))
      (node (ref "U$43") (pin "R-") (pinfunction "R-_R-") (pintype "bidirectional"))
    )
    (net (code "173") (name "Net-(R$44-PadP$1)") (class "Default")
      (node (ref "R$44") (pin "P$1") (pinfunction "P$1_P$1") (pintype "bidirectional"))
      (node (ref "U$44") (pin "R-") (pinfunction "R-_R-") (pintype "bidirectional"))
    )
    (net (code "174") (name "Net-(R$45-PadP$1)") (class "Default")
      (node (ref "R$45") (pin "P$1") (pinfunction "P$1_P$1") (pintype "bidirectional"))
      (node (ref "U$45") (pin "R-") (pinfunction "R-_R-") (pintype "bidirectional"))
    )
    (net (code "175") (name "Net-(R$46-PadP$1)") (class "Default")
      (node (ref "R$46") (pin "P$1") (pinfunction "P$1_P$1") (pintype "bidirectional"))
      (node (ref "U$46") (pin "R-") (pinfunction "R-_R-") (pintype "bidirectional"))
    )
    (net (code "176") (name "Net-(R$47-PadP$1)") (class "Default")
      (node (ref "R$47") (pin "P$1") (pinfunction "P$1_P$1") (pintype "bidirectional"))
      (node (ref "U$47") (pin "R-") (pinfunction "R-_R-") (pintype "bidirectional"))
    )
    (net (code "177") (name "Net-(R$48-PadP$1)") (class "Default")
      (node (ref "R$48") (pin "P$1") (pinfunction "P$1_P$1") (pintype "bidirectional"))
      (node (ref "U$48") (pin "R-") (pinfunction "R-_R-") (pintype "bidirectional"))
    )
    (net (code "178") (name "Net-(R$49-PadP$1)") (class "Default")
      (node (ref "R$49") (pin "P$1") (pinfunction "P$1_P$1") (pintype "bidirectional"))
      (node (ref "U$49") (pin "R-") (pinfunction "R-_R-") (pintype "bidirectional"))
    )
    (net (code "179") (name "Net-(R$50-PadP$1)") (class "Default")
      (node (ref "R$50") (pin "P$1") (pinfunction "P$1_P$1") (pintype "bidirectional"))
      (node (ref "U$50") (pin "R-") (pinfunction "R-_R-") (pintype "bidirectional"))
    )
    (net (code "180") (name "Net-(R$51-PadP$1)") (class "Default")
      (node (ref "R$51") (pin "P$1") (pinfunction "P$1_P$1") (pintype "bidirectional"))
      (node (ref "U$51") (pin "R-") (pinfunction "R-_R-") (pintype "bidirectional"))
    )
    (net (code "181") (name "Net-(R$52-PadP$1)") (class "Default")
      (node (ref "R$52") (pin "P$1") (pinfunction "P$1_P$1") (pintype "bidirectional"))
      (node (ref "U$52") (pin "R-") (pinfunction "R-_R-") (pintype "bidirectional"))
    )
    (net (code "182") (name "Net-(R$53-PadP$1)") (class "Default")
      (node (ref "R$53") (pin "P$1") (pinfunction "P$1_P$1") (pintype "bidirectional"))
      (node (ref "U$53") (pin "R-") (pinfunction "R-_R-") (pintype "bidirectional"))
    )
    (net (code "183") (name "Net-(R$54-PadP$1)") (class "Default")
      (node (ref "R$54") (pin "P$1") (pinfunction "P$1_P$1") (pintype "bidirectional"))
      (node (ref "U$54") (pin "R-") (pinfunction "R-_R-") (pintype "bidirectional"))
    )
    (net (code "184") (name "Net-(R$55-PadP$1)") (class "Default")
      (node (ref "R$55") (pin "P$1") (pinfunction "P$1_P$1") (pintype "bidirectional"))
      (node (ref "U$55") (pin "R-") (pinfunction "R-_R-") (pintype "bidirectional"))
    )
    (net (code "185") (name "Net-(R$56-PadP$1)") (class "Default")
      (node (ref "R$56") (pin "P$1") (pinfunction "P$1_P$1") (pintype "bidirectional"))
      (node (ref "U$56") (pin "R-") (pinfunction "R-_R-") (pintype "bidirectional"))
    )
    (net (code "186") (name "Net-(R$57-PadP$1)") (class "Default")
      (node (ref "R$57") (pin "P$1") (pinfunction "P$1_P$1") (pintype "bidirectional"))
      (node (ref "U$57") (pin "R-") (pinfunction "R-_R-") (pintype "bidirectional"))
    )
    (net (code "187") (name "Net-(R$58-PadP$1)") (class "Default")
      (node (ref "R$58") (pin "P$1") (pinfunction "P$1_P$1") (pintype "bidirectional"))
      (node (ref "U$58") (pin "R-") (pinfunction "R-_R-") (pintype "bidirectional"))
    )
    (net (code "188") (name "Net-(R$59-PadP$1)") (class "Default")
      (node (ref "R$59") (pin "P$1") (pinfunction "P$1_P$1") (pintype "bidirectional"))
      (node (ref "U$59") (pin "R-") (pinfunction "R-_R-") (pintype "bidirectional"))
    )
    (net (code "189") (name "Net-(R$60-PadP$1)") (class "Default")
      (node (ref "R$60") (pin "P$1") (pinfunction "P$1_P$1") (pintype "bidirectional"))
      (node (ref "U$60") (pin "R-") (pinfunction "R-_R-") (pintype "bidirectional"))
    )
    (net (code "190") (name "Net-(R$61-PadP$1)") (class "Default")
      (node (ref "R$61") (pin "P$1") (pinfunction "P$1_P$1") (pintype "bidirectional"))
      (node (ref "U$61") (pin "R-") (pinfunction "R-_R-") (pintype "bidirectional"))
    )
    (net (code "191") (name "Net-(R$62-PadP$1)") (class "Default")
      (node (ref "R$62") (pin "P$1") (pinfunction "P$1_P$1") (pintype "bidirectional"))
      (node (ref "U$62") (pin "R-") (pinfunction "R-_R-") (pintype "bidirectional"))
    )
    (net (code "192") (name "Net-(R$63-PadP$1)") (class "Default")
      (node (ref "R$63") (pin "P$1") (pinfunction "P$1_P$1") (pintype "bidirectional"))
      (node (ref "U$63") (pin "R-") (pinfunction "R-_R-") (pintype "bidirectional"))
    )
    (net (code "193") (name "Net-(R$64-PadP$1)") (class "Default")
      (node (ref "R$64") (pin "P$1") (pinfunction "P$1_P$1") (pintype "bidirectional"))
      (node (ref "U$64") (pin "R-") (pinfunction "R-_R-") (pintype "bidirectional"))
    )
  )
)
